# SCH_MX80_I_MOTHERBOARD.net
KiCad netlist of a schematic drawn in EasyEDA
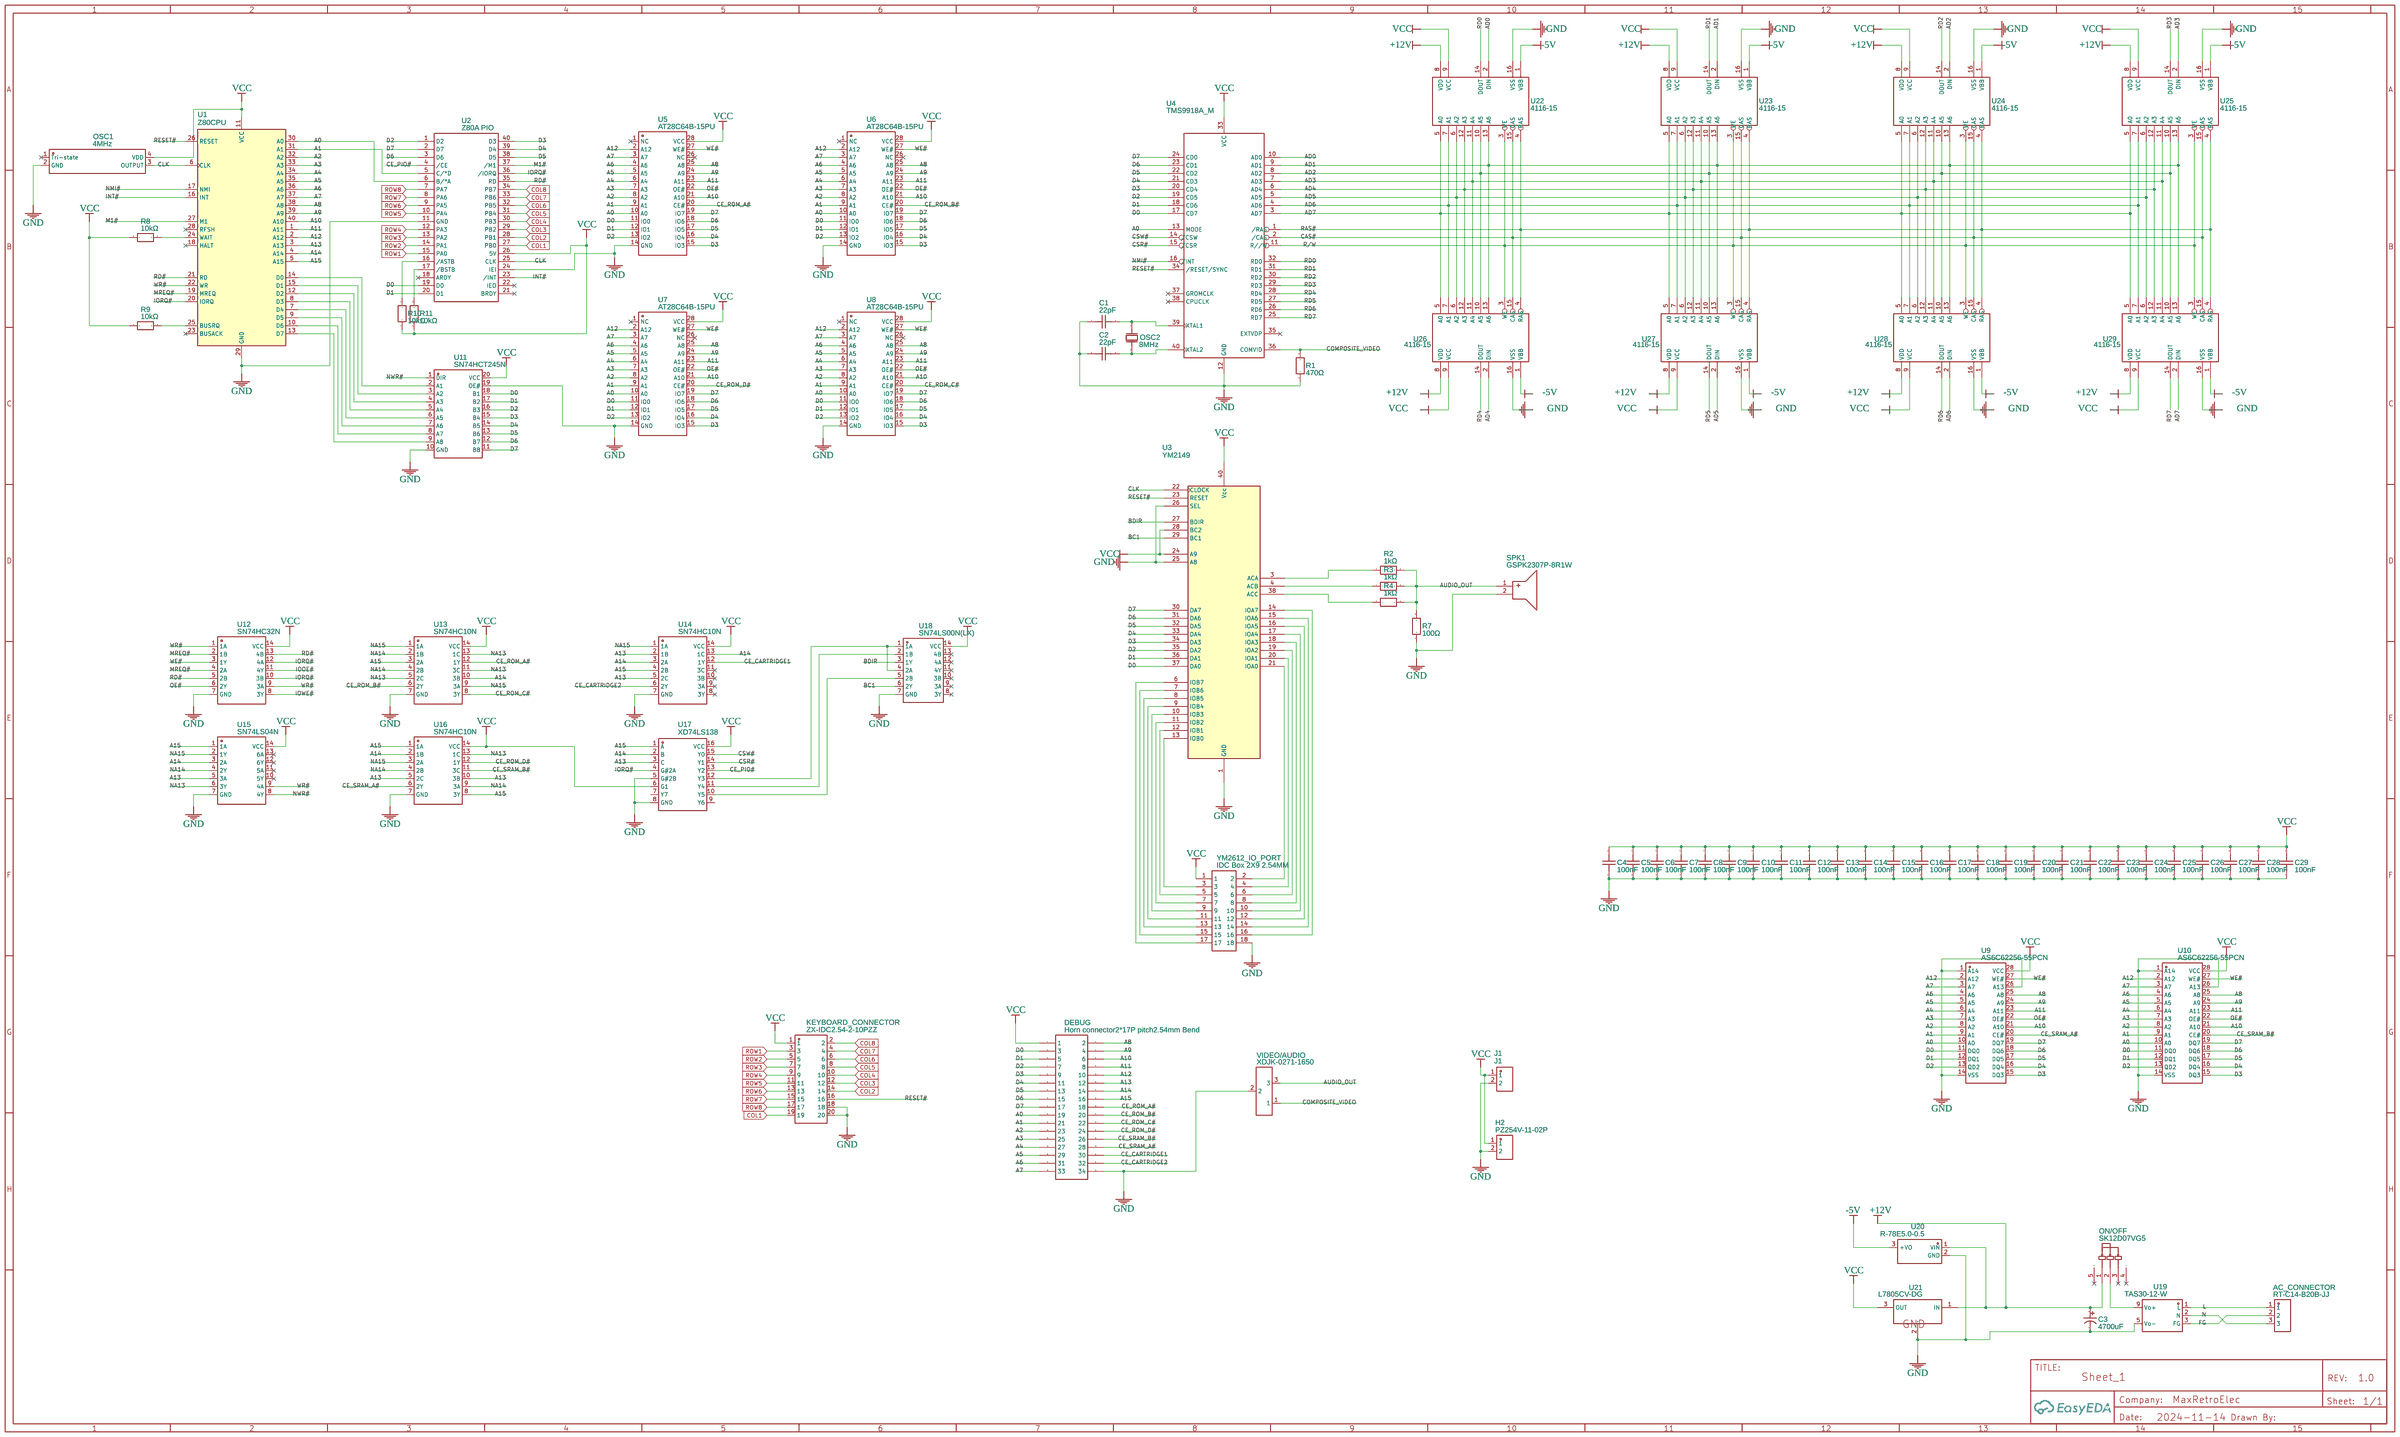
[diagram p0: schematic sheet]

(export (version "E")
  (design (tool "Eeschema 10.0.6"))
  (components
    (comp (ref "AC_CONNECTOR")
      (value "RT-C14-B20B-JJ")
      (fields (field (name "Manufacturer") "Legion(六钧)"))
      (libsource (lib "") (part "RT-C14-B20B-JJ"))
    )
    (comp (ref "C1")
      (value "22pF")
      (fields (field (name "Manufacturer Part") "CC45SL3JD220JYNNA") (field (name "Manufacturer") "TDK"))
      (libsource (lib "") (part "CC45SL3JD220JYNNA"))
    )
    (comp (ref "C2")
      (value "22pF")
      (fields (field (name "Manufacturer Part") "CC45SL3JD220JYNNA") (field (name "Manufacturer") "TDK"))
      (libsource (lib "") (part "CC45SL3JD220JYNNA"))
    )
    (comp (ref "C3")
      (value "4700uF")
      (fields
        (field (name "Manufacturer Part") "KM478M025K30RR0VH2FP0")
        (field (name "Manufacturer") "CX(承兴)")
      )
      (libsource (lib "") (part "4700uF25V"))
    )
    (comp (ref "C4")
      (value "100nF")
      (fields
        (field (name "Manufacturer Part") "CC1H104ZC74D3F5O30MN")
        (field (name "Manufacturer") "Dersonic(德尔创)")
      )
      (libsource (lib "") (part "CC1H104ZC74D3F5O30MN"))
    )
    (comp (ref "C5")
      (value "100nF")
      (fields
        (field (name "Manufacturer Part") "CC1H104ZC74D3F5O30MN")
        (field (name "Manufacturer") "Dersonic(德尔创)")
      )
      (libsource (lib "") (part "CC1H104ZC74D3F5O30MN"))
    )
    (comp (ref "C6")
      (value "100nF")
      (fields
        (field (name "Manufacturer Part") "CC1H104ZC74D3F5O30MN")
        (field (name "Manufacturer") "Dersonic(德尔创)")
      )
      (libsource (lib "") (part "CC1H104ZC74D3F5O30MN"))
    )
    (comp (ref "C7")
      (value "100nF")
      (fields
        (field (name "Manufacturer Part") "CC1H104ZC74D3F5O30MN")
        (field (name "Manufacturer") "Dersonic(德尔创)")
      )
      (libsource (lib "") (part "CC1H104ZC74D3F5O30MN"))
    )
    (comp (ref "C8")
      (value "100nF")
      (fields
        (field (name "Manufacturer Part") "CC1H104ZC74D3F5O30MN")
        (field (name "Manufacturer") "Dersonic(德尔创)")
      )
      (libsource (lib "") (part "CC1H104ZC74D3F5O30MN"))
    )
    (comp (ref "C9")
      (value "100nF")
      (fields
        (field (name "Manufacturer Part") "CC1H104ZC74D3F5O30MN")
        (field (name "Manufacturer") "Dersonic(德尔创)")
      )
      (libsource (lib "") (part "CC1H104ZC74D3F5O30MN"))
    )
    (comp (ref "C10")
      (value "100nF")
      (fields
        (field (name "Manufacturer Part") "CC1H104ZC74D3F5O30MN")
        (field (name "Manufacturer") "Dersonic(德尔创)")
      )
      (libsource (lib "") (part "CC1H104ZC74D3F5O30MN"))
    )
    (comp (ref "C11")
      (value "100nF")
      (fields
        (field (name "Manufacturer Part") "CC1H104ZC74D3F5O30MN")
        (field (name "Manufacturer") "Dersonic(德尔创)")
      )
      (libsource (lib "") (part "CC1H104ZC74D3F5O30MN"))
    )
    (comp (ref "C12")
      (value "100nF")
      (fields
        (field (name "Manufacturer Part") "CC1H104ZC74D3F5O30MN")
        (field (name "Manufacturer") "Dersonic(德尔创)")
      )
      (libsource (lib "") (part "CC1H104ZC74D3F5O30MN"))
    )
    (comp (ref "C13")
      (value "100nF")
      (fields
        (field (name "Manufacturer Part") "CC1H104ZC74D3F5O30MN")
        (field (name "Manufacturer") "Dersonic(德尔创)")
      )
      (libsource (lib "") (part "CC1H104ZC74D3F5O30MN"))
    )
    (comp (ref "C14")
      (value "100nF")
      (fields
        (field (name "Manufacturer Part") "CC1H104ZC74D3F5O30MN")
        (field (name "Manufacturer") "Dersonic(德尔创)")
      )
      (libsource (lib "") (part "CC1H104ZC74D3F5O30MN"))
    )
    (comp (ref "C15")
      (value "100nF")
      (fields
        (field (name "Manufacturer Part") "CC1H104ZC74D3F5O30MN")
        (field (name "Manufacturer") "Dersonic(德尔创)")
      )
      (libsource (lib "") (part "CC1H104ZC74D3F5O30MN"))
    )
    (comp (ref "C16")
      (value "100nF")
      (fields
        (field (name "Manufacturer Part") "CC1H104ZC74D3F5O30MN")
        (field (name "Manufacturer") "Dersonic(德尔创)")
      )
      (libsource (lib "") (part "CC1H104ZC74D3F5O30MN"))
    )
    (comp (ref "C17")
      (value "100nF")
      (fields
        (field (name "Manufacturer Part") "CC1H104ZC74D3F5O30MN")
        (field (name "Manufacturer") "Dersonic(德尔创)")
      )
      (libsource (lib "") (part "CC1H104ZC74D3F5O30MN"))
    )
    (comp (ref "C18")
      (value "100nF")
      (fields
        (field (name "Manufacturer Part") "CC1H104ZC74D3F5O30MN")
        (field (name "Manufacturer") "Dersonic(德尔创)")
      )
      (libsource (lib "") (part "CC1H104ZC74D3F5O30MN"))
    )
    (comp (ref "C19")
      (value "100nF")
      (fields
        (field (name "Manufacturer Part") "CC1H104ZC74D3F5O30MN")
        (field (name "Manufacturer") "Dersonic(德尔创)")
      )
      (libsource (lib "") (part "CC1H104ZC74D3F5O30MN"))
    )
    (comp (ref "C20")
      (value "100nF")
      (fields
        (field (name "Manufacturer Part") "CC1H104ZC74D3F5O30MN")
        (field (name "Manufacturer") "Dersonic(德尔创)")
      )
      (libsource (lib "") (part "CC1H104ZC74D3F5O30MN"))
    )
    (comp (ref "C21")
      (value "100nF")
      (fields
        (field (name "Manufacturer Part") "CC1H104ZC74D3F5O30MN")
        (field (name "Manufacturer") "Dersonic(德尔创)")
      )
      (libsource (lib "") (part "CC1H104ZC74D3F5O30MN"))
    )
    (comp (ref "C22")
      (value "100nF")
      (fields
        (field (name "Manufacturer Part") "CC1H104ZC74D3F5O30MN")
        (field (name "Manufacturer") "Dersonic(德尔创)")
      )
      (libsource (lib "") (part "CC1H104ZC74D3F5O30MN"))
    )
    (comp (ref "C23")
      (value "100nF")
      (fields
        (field (name "Manufacturer Part") "CC1H104ZC74D3F5O30MN")
        (field (name "Manufacturer") "Dersonic(德尔创)")
      )
      (libsource (lib "") (part "CC1H104ZC74D3F5O30MN"))
    )
    (comp (ref "C24")
      (value "100nF")
      (fields
        (field (name "Manufacturer Part") "CC1H104ZC74D3F5O30MN")
        (field (name "Manufacturer") "Dersonic(德尔创)")
      )
      (libsource (lib "") (part "CC1H104ZC74D3F5O30MN"))
    )
    (comp (ref "C25")
      (value "100nF")
      (fields
        (field (name "Manufacturer Part") "CC1H104ZC74D3F5O30MN")
        (field (name "Manufacturer") "Dersonic(德尔创)")
      )
      (libsource (lib "") (part "CC1H104ZC74D3F5O30MN"))
    )
    (comp (ref "C26")
      (value "100nF")
      (fields
        (field (name "Manufacturer Part") "CC1H104ZC74D3F5O30MN")
        (field (name "Manufacturer") "Dersonic(德尔创)")
      )
      (libsource (lib "") (part "CC1H104ZC74D3F5O30MN"))
    )
    (comp (ref "C27")
      (value "100nF")
      (fields
        (field (name "Manufacturer Part") "CC1H104ZC74D3F5O30MN")
        (field (name "Manufacturer") "Dersonic(德尔创)")
      )
      (libsource (lib "") (part "CC1H104ZC74D3F5O30MN"))
    )
    (comp (ref "C28")
      (value "100nF")
      (fields
        (field (name "Manufacturer Part") "CC1H104ZC74D3F5O30MN")
        (field (name "Manufacturer") "Dersonic(德尔创)")
      )
      (libsource (lib "") (part "CC1H104ZC74D3F5O30MN"))
    )
    (comp (ref "C29")
      (value "100nF")
      (fields
        (field (name "Manufacturer Part") "CC1H104ZC74D3F5O30MN")
        (field (name "Manufacturer") "Dersonic(德尔创)")
      )
      (libsource (lib "") (part "CC1H104ZC74D3F5O30MN"))
    )
    (comp (ref "DEBUG")
      (value "Horn connector2*17P pitch2.54mm Bend")
      (fields
        (field (name "Manufacturer Part") "2.54-2*17P弯简牛")
        (field (name "Manufacturer") "BOOMELE(博穆精密)")
      )
      (libsource (lib "") (part "Horn connector2*17P pitch2.54mm Bend"))
    )
    (comp (ref "H2")
      (value "PZ254V-11-02P")
      (fields (field (name "Manufacturer") "XFCN(兴飞)"))
      (libsource (lib "") (part "PZ254V-11-02P"))
    )
    (comp (ref "J1")
      (value "J1")
      (fields
        (field (name "Manufacturer Part") "ZX-PM2.54-1-2PY")
        (field (name "Manufacturer") "Megastar(兆星)")
      )
      (libsource (lib "") (part "ZX-PM2.54-1-2PY"))
    )
    (comp (ref "KEYBOARD_CONNECTOR")
      (value "ZX-IDC2.54-2-10PZZ")
      (fields (field (name "Manufacturer") "Megastar(兆星)"))
      (libsource (lib "") (part "ZX-IDC2.54-2-10PZZ"))
    )
    (comp (ref "ON/OFF")
      (value "SK12D07VG5")
      (fields (field (name "Manufacturer") "SHOU HAN(首韩)"))
      (libsource (lib "") (part "SK12D07VG5"))
    )
    (comp (ref "OSC1")
      (value "4MHz")
      (fields
        (field (name "Manufacturer Part") "S7D4.000000B20F30T")
        (field (name "Manufacturer") "SCTF(星通时频)")
      )
      (libsource (lib "") (part "S7D4.000000B20F30T"))
    )
    (comp (ref "OSC2")
      (value "8MHz")
      (fields (field (name "Manufacturer Part") "X49SD8MSD2SC") (field (name "Manufacturer") "YXC(扬兴晶振)"))
      (libsource (lib "") (part "X49SD8MSD2SC"))
    )
    (comp (ref "R1")
      (value "470Ω")
      (fields (field (name "Manufacturer Part") "CF1/4W-470Ω±5%T52") (field (name "Manufacturer") "华星机电"))
      (libsource (lib "") (part "CF1/4W-470Ω±5%T52"))
    )
    (comp (ref "R2")
      (value "1kΩ")
      (fields (field (name "Manufacturer Part") "CR1/4W-1K±5%-ST52") (field (name "Manufacturer") "VO(翔胜)"))
      (libsource (lib "") (part "CR1/4W-1K±5%-ST52"))
    )
    (comp (ref "R3")
      (value "1kΩ")
      (fields (field (name "Manufacturer Part") "CR1/4W-1K±5%-ST52") (field (name "Manufacturer") "VO(翔胜)"))
      (libsource (lib "") (part "CR1/4W-1K±5%-ST52"))
    )
    (comp (ref "R4")
      (value "1kΩ")
      (fields (field (name "Manufacturer Part") "CR1/4W-1K±5%-ST52") (field (name "Manufacturer") "VO(翔胜)"))
      (libsource (lib "") (part "CR1/4W-1K±5%-ST52"))
    )
    (comp (ref "R7")
      (value "100Ω")
      (fields (field (name "Manufacturer Part") "CR1/4W-100Ω±5%-ST52") (field (name "Manufacturer") "VO(翔胜)"))
      (libsource (lib "") (part "CR1/4W-100Ω±5%-ST52"))
    )
    (comp (ref "R8")
      (value "10kΩ")
      (fields (field (name "Manufacturer Part") "CR1/4W-10K±5%-ST52") (field (name "Manufacturer") "VO(翔胜)"))
      (libsource (lib "") (part "CR1/4W-10K±5%-ST52_1"))
    )
    (comp (ref "R9")
      (value "10kΩ")
      (fields (field (name "Manufacturer Part") "CR1/4W-10K±5%-ST52") (field (name "Manufacturer") "VO(翔胜)"))
      (libsource (lib "") (part "CR1/4W-10K±5%-ST52_1"))
    )
    (comp (ref "R10")
      (value "10kΩ")
      (fields (field (name "Manufacturer Part") "CR1/4W-10K±5%-ST52") (field (name "Manufacturer") "VO(翔胜)"))
      (libsource (lib "") (part "CR1/4W-10K±5%-ST52"))
    )
    (comp (ref "R11")
      (value "10kΩ")
      (fields (field (name "Manufacturer Part") "CR1/4W-10K±5%-ST52") (field (name "Manufacturer") "VO(翔胜)"))
      (libsource (lib "") (part "CR1/4W-10K±5%-ST52"))
    )
    (comp (ref "SPK1")
      (value "GSPK2307P-8R1W")
      (fields (field (name "Manufacturer") "INGHAi(赢海)"))
      (libsource (lib "") (part "GSPK2307P-8R1W"))
    )
    (comp (ref "U1") (value "Z80CPU") (libsource (lib "") (part "Z80CPU")))
    (comp (ref "U2") (value "Z80A PIO") (libsource (lib "") (part "Z80A PIO")))
    (comp (ref "U3") (value "YM2149") (libsource (lib "") (part "YM2149")))
    (comp (ref "U4") (value "TMS9918A_M") (libsource (lib "") (part "TMS9918A_M")))
    (comp (ref "U5")
      (value "AT28C64B-15PU")
      (fields (field (name "Manufacturer") "MICROCHIP(美国微芯)"))
      (libsource (lib "") (part "AT28C64B-15PU"))
    )
    (comp (ref "U6")
      (value "AT28C64B-15PU")
      (fields (field (name "Manufacturer") "MICROCHIP(美国微芯)"))
      (libsource (lib "") (part "AT28C64B-15PU"))
    )
    (comp (ref "U7")
      (value "AT28C64B-15PU")
      (fields (field (name "Manufacturer") "MICROCHIP(美国微芯)"))
      (libsource (lib "") (part "AT28C64B-15PU"))
    )
    (comp (ref "U8")
      (value "AT28C64B-15PU")
      (fields (field (name "Manufacturer") "MICROCHIP(美国微芯)"))
      (libsource (lib "") (part "AT28C64B-15PU"))
    )
    (comp (ref "U9")
      (value "AS6C62256-55PCN")
      (fields (field (name "Manufacturer") "Alliance Memory"))
      (libsource (lib "") (part "AS6C62256-55PCN"))
    )
    (comp (ref "U10")
      (value "AS6C62256-55PCN")
      (fields (field (name "Manufacturer") "Alliance Memory"))
      (libsource (lib "") (part "AS6C62256-55PCN"))
    )
    (comp (ref "U11")
      (value "SN74HCT245N")
      (fields (field (name "Manufacturer") "TI(德州仪器)"))
      (libsource (lib "") (part "SN74HCT245N"))
    )
    (comp (ref "U12")
      (value "SN74HC32N")
      (fields (field (name "Manufacturer") "TI(德州仪器)"))
      (libsource (lib "") (part "SN74HC32N"))
    )
    (comp (ref "U13")
      (value "SN74HC10N")
      (fields (field (name "Manufacturer") "TI(德州仪器)"))
      (libsource (lib "") (part "SN74HC10N"))
    )
    (comp (ref "U14")
      (value "SN74HC10N")
      (fields (field (name "Manufacturer") "TI(德州仪器)"))
      (libsource (lib "") (part "SN74HC10N"))
    )
    (comp (ref "U15")
      (value "SN74LS04N")
      (fields (field (name "Manufacturer") "TI(德州仪器)"))
      (libsource (lib "") (part "SN74LS04N"))
    )
    (comp (ref "U16")
      (value "SN74HC10N")
      (fields (field (name "Manufacturer") "TI(德州仪器)"))
      (libsource (lib "") (part "SN74HC10N"))
    )
    (comp (ref "U17")
      (value "XD74LS138")
      (fields (field (name "Manufacturer") "XINLUDA(信路达)"))
      (libsource (lib "") (part "XD74LS138"))
    )
    (comp (ref "U18")
      (value "SN74LS00N(LX)")
      (fields (field (name "Manufacturer") "LX(灵星芯微)"))
      (libsource (lib "") (part "SN74LS00N(LX)"))
    )
    (comp (ref "U19")
      (value "TAS30-12-W")
      (fields (field (name "Manufacturer") "TDPOWER(腾达电源)"))
      (libsource (lib "") (part "TAS30-12-W"))
    )
    (comp (ref "U20")
      (value "R-78E5.0-0.5")
      (fields (field (name "Manufacturer") "YLPTEC(易川)"))
      (libsource (lib "") (part "R-78E5.0-0.5"))
    )
    (comp (ref "U21")
      (value "L7805CV-DG")
      (fields (field (name "Manufacturer") "ST(意法半导体)"))
      (libsource (lib "") (part "L7805CV-DG"))
    )
    (comp (ref "U22")
      (value "4116-15")
      (fields (field (name "Manufacturer") "Major Brands"))
      (libsource (lib "") (part "4116-15"))
    )
    (comp (ref "U23")
      (value "4116-15")
      (fields (field (name "Manufacturer") "Major Brands"))
      (libsource (lib "") (part "4116-15"))
    )
    (comp (ref "U24")
      (value "4116-15")
      (fields (field (name "Manufacturer") "Major Brands"))
      (libsource (lib "") (part "4116-15"))
    )
    (comp (ref "U25")
      (value "4116-15")
      (fields (field (name "Manufacturer") "Major Brands"))
      (libsource (lib "") (part "4116-15"))
    )
    (comp (ref "U26")
      (value "4116-15")
      (fields (field (name "Manufacturer") "Major Brands"))
      (libsource (lib "") (part "4116-15_1"))
    )
    (comp (ref "U27")
      (value "4116-15")
      (fields (field (name "Manufacturer") "Major Brands"))
      (libsource (lib "") (part "4116-15_1"))
    )
    (comp (ref "U28")
      (value "4116-15")
      (fields (field (name "Manufacturer") "Major Brands"))
      (libsource (lib "") (part "4116-15_1"))
    )
    (comp (ref "U29")
      (value "4116-15")
      (fields (field (name "Manufacturer") "Major Brands"))
      (libsource (lib "") (part "4116-15_1"))
    )
    (comp (ref "VIDEO/AUDIO")
      (value "XDJK-0271-1650")
      (fields (field (name "Manufacturer") "LX(连欣科技)"))
      (libsource (lib "") (part "XDJK-0271-1650"))
    )
    (comp (ref "YM2612_IO_PORT")
      (value "IDC Box 2X9 2.54MM")
      (fields
        (field (name "Manufacturer Part") "2.54-2*9P 弯 简牛")
        (field (name "Manufacturer") "BOOMELE(博穆精密)")
      )
      (libsource (lib "") (part "IDC Box 2X9 2.54MM"))
    )
  )
  (nets
    (net (code "1") (name "+12V") (class "Default")
      (node (ref "C3") (pin "1") (pinfunction "1_1") (pintype "input"))
      (node (ref "ON/OFF") (pin "1") (pinfunction "1_1") (pintype "unspecified"))
      (node (ref "U20") (pin "1") (pinfunction "VIN_1") (pintype "unspecified"))
      (node (ref "U21") (pin "1") (pinfunction "IN_1") (pintype "passive"))
      (node (ref "U22") (pin "8") (pinfunction "VDD_8") (pintype "unspecified"))
      (node (ref "U23") (pin "8") (pinfunction "VDD_8") (pintype "unspecified"))
      (node (ref "U24") (pin "8") (pinfunction "VDD_8") (pintype "unspecified"))
      (node (ref "U25") (pin "8") (pinfunction "VDD_8") (pintype "unspecified"))
      (node (ref "U26") (pin "8") (pinfunction "VDD_8") (pintype "unspecified"))
      (node (ref "U27") (pin "8") (pinfunction "VDD_8") (pintype "unspecified"))
      (node (ref "U28") (pin "8") (pinfunction "VDD_8") (pintype "unspecified"))
      (node (ref "U29") (pin "8") (pinfunction "VDD_8") (pintype "unspecified"))
    )
    (net (code "2") (name "-5V") (class "Default")
      (node (ref "U20") (pin "3") (pinfunction "+VO_3") (pintype "unspecified"))
      (node (ref "U22") (pin "1") (pinfunction "VBB_1") (pintype "unspecified"))
      (node (ref "U23") (pin "1") (pinfunction "VBB_1") (pintype "unspecified"))
      (node (ref "U24") (pin "1") (pinfunction "VBB_1") (pintype "unspecified"))
      (node (ref "U25") (pin "1") (pinfunction "VBB_1") (pintype "unspecified"))
      (node (ref "U26") (pin "1") (pinfunction "VBB_1") (pintype "unspecified"))
      (node (ref "U27") (pin "1") (pinfunction "VBB_1") (pintype "unspecified"))
      (node (ref "U28") (pin "1") (pinfunction "VBB_1") (pintype "unspecified"))
      (node (ref "U29") (pin "1") (pinfunction "VBB_1") (pintype "unspecified"))
    )
    (net (code "3") (name "/A0") (class "Default")
      (node (ref "DEBUG") (pin "19") (pinfunction "19_19") (pintype "unspecified"))
      (node (ref "U1") (pin "30") (pinfunction "A0_30") (pintype "output"))
      (node (ref "U10") (pin "10") (pinfunction "A0_10") (pintype "unspecified"))
      (node (ref "U2") (pin "6") (pinfunction "B/*A_6") (pintype "unspecified"))
      (node (ref "U4") (pin "13") (pinfunction "MODE_13") (pintype "unspecified"))
      (node (ref "U5") (pin "10") (pinfunction "A0_10") (pintype "unspecified"))
      (node (ref "U6") (pin "10") (pinfunction "A0_10") (pintype "unspecified"))
      (node (ref "U7") (pin "10") (pinfunction "A0_10") (pintype "unspecified"))
      (node (ref "U8") (pin "10") (pinfunction "A0_10") (pintype "unspecified"))
      (node (ref "U9") (pin "10") (pinfunction "A0_10") (pintype "unspecified"))
    )
    (net (code "4") (name "/A1") (class "Default")
      (node (ref "DEBUG") (pin "21") (pinfunction "21_21") (pintype "unspecified"))
      (node (ref "U1") (pin "31") (pinfunction "A1_31") (pintype "output"))
      (node (ref "U10") (pin "9") (pinfunction "A1_9") (pintype "unspecified"))
      (node (ref "U2") (pin "5") (pinfunction "C/*D_5") (pintype "unspecified"))
      (node (ref "U5") (pin "9") (pinfunction "A1_9") (pintype "unspecified"))
      (node (ref "U6") (pin "9") (pinfunction "A1_9") (pintype "unspecified"))
      (node (ref "U7") (pin "9") (pinfunction "A1_9") (pintype "unspecified"))
      (node (ref "U8") (pin "9") (pinfunction "A1_9") (pintype "unspecified"))
      (node (ref "U9") (pin "9") (pinfunction "A1_9") (pintype "unspecified"))
    )
    (net (code "5") (name "/A2") (class "Default")
      (node (ref "DEBUG") (pin "23") (pinfunction "23_23") (pintype "unspecified"))
      (node (ref "U1") (pin "32") (pinfunction "A2_32") (pintype "output"))
      (node (ref "U10") (pin "8") (pinfunction "A2_8") (pintype "unspecified"))
      (node (ref "U5") (pin "8") (pinfunction "A2_8") (pintype "unspecified"))
      (node (ref "U6") (pin "8") (pinfunction "A2_8") (pintype "unspecified"))
      (node (ref "U7") (pin "8") (pinfunction "A2_8") (pintype "unspecified"))
      (node (ref "U8") (pin "8") (pinfunction "A2_8") (pintype "unspecified"))
      (node (ref "U9") (pin "8") (pinfunction "A2_8") (pintype "unspecified"))
    )
    (net (code "6") (name "/A3") (class "Default")
      (node (ref "DEBUG") (pin "25") (pinfunction "25_25") (pintype "unspecified"))
      (node (ref "U1") (pin "33") (pinfunction "A3_33") (pintype "output"))
      (node (ref "U10") (pin "7") (pinfunction "A3_7") (pintype "unspecified"))
      (node (ref "U5") (pin "7") (pinfunction "A3_7") (pintype "unspecified"))
      (node (ref "U6") (pin "7") (pinfunction "A3_7") (pintype "unspecified"))
      (node (ref "U7") (pin "7") (pinfunction "A3_7") (pintype "unspecified"))
      (node (ref "U8") (pin "7") (pinfunction "A3_7") (pintype "unspecified"))
      (node (ref "U9") (pin "7") (pinfunction "A3_7") (pintype "unspecified"))
    )
    (net (code "7") (name "/A4") (class "Default")
      (node (ref "DEBUG") (pin "27") (pinfunction "27_27") (pintype "unspecified"))
      (node (ref "U1") (pin "34") (pinfunction "A4_34") (pintype "output"))
      (node (ref "U10") (pin "6") (pinfunction "A4_6") (pintype "unspecified"))
      (node (ref "U5") (pin "6") (pinfunction "A4_6") (pintype "unspecified"))
      (node (ref "U6") (pin "6") (pinfunction "A4_6") (pintype "unspecified"))
      (node (ref "U7") (pin "6") (pinfunction "A4_6") (pintype "unspecified"))
      (node (ref "U8") (pin "6") (pinfunction "A4_6") (pintype "unspecified"))
      (node (ref "U9") (pin "6") (pinfunction "A4_6") (pintype "unspecified"))
    )
    (net (code "8") (name "/A5") (class "Default")
      (node (ref "DEBUG") (pin "29") (pinfunction "29_29") (pintype "unspecified"))
      (node (ref "U1") (pin "35") (pinfunction "A5_35") (pintype "output"))
      (node (ref "U10") (pin "5") (pinfunction "A5_5") (pintype "unspecified"))
      (node (ref "U5") (pin "5") (pinfunction "A5_5") (pintype "unspecified"))
      (node (ref "U6") (pin "5") (pinfunction "A5_5") (pintype "unspecified"))
      (node (ref "U7") (pin "5") (pinfunction "A5_5") (pintype "unspecified"))
      (node (ref "U8") (pin "5") (pinfunction "A5_5") (pintype "unspecified"))
      (node (ref "U9") (pin "5") (pinfunction "A5_5") (pintype "unspecified"))
    )
    (net (code "9") (name "/A6") (class "Default")
      (node (ref "DEBUG") (pin "31") (pinfunction "31_31") (pintype "unspecified"))
      (node (ref "U1") (pin "36") (pinfunction "A6_36") (pintype "output"))
      (node (ref "U10") (pin "4") (pinfunction "A6_4") (pintype "unspecified"))
      (node (ref "U5") (pin "4") (pinfunction "A6_4") (pintype "unspecified"))
      (node (ref "U6") (pin "4") (pinfunction "A6_4") (pintype "unspecified"))
      (node (ref "U7") (pin "4") (pinfunction "A6_4") (pintype "unspecified"))
      (node (ref "U8") (pin "4") (pinfunction "A6_4") (pintype "unspecified"))
      (node (ref "U9") (pin "4") (pinfunction "A6_4") (pintype "unspecified"))
    )
    (net (code "10") (name "/A7") (class "Default")
      (node (ref "DEBUG") (pin "33") (pinfunction "33_33") (pintype "unspecified"))
      (node (ref "U1") (pin "37") (pinfunction "A7_37") (pintype "output"))
      (node (ref "U10") (pin "3") (pinfunction "A7_3") (pintype "unspecified"))
      (node (ref "U5") (pin "3") (pinfunction "A7_3") (pintype "unspecified"))
      (node (ref "U6") (pin "3") (pinfunction "A7_3") (pintype "unspecified"))
      (node (ref "U7") (pin "3") (pinfunction "A7_3") (pintype "unspecified"))
      (node (ref "U8") (pin "3") (pinfunction "A7_3") (pintype "unspecified"))
      (node (ref "U9") (pin "3") (pinfunction "A7_3") (pintype "unspecified"))
    )
    (net (code "11") (name "/A8") (class "Default")
      (node (ref "DEBUG") (pin "2") (pinfunction "2_2") (pintype "unspecified"))
      (node (ref "U1") (pin "38") (pinfunction "A8_38") (pintype "output"))
      (node (ref "U10") (pin "25") (pinfunction "A8_25") (pintype "unspecified"))
      (node (ref "U5") (pin "25") (pinfunction "A8_25") (pintype "unspecified"))
      (node (ref "U6") (pin "25") (pinfunction "A8_25") (pintype "unspecified"))
      (node (ref "U7") (pin "25") (pinfunction "A8_25") (pintype "unspecified"))
      (node (ref "U8") (pin "25") (pinfunction "A8_25") (pintype "unspecified"))
      (node (ref "U9") (pin "25") (pinfunction "A8_25") (pintype "unspecified"))
    )
    (net (code "12") (name "/A9") (class "Default")
      (node (ref "DEBUG") (pin "4") (pinfunction "4_4") (pintype "unspecified"))
      (node (ref "U1") (pin "39") (pinfunction "A9_39") (pintype "output"))
      (node (ref "U10") (pin "24") (pinfunction "A9_24") (pintype "unspecified"))
      (node (ref "U5") (pin "24") (pinfunction "A9_24") (pintype "unspecified"))
      (node (ref "U6") (pin "24") (pinfunction "A9_24") (pintype "unspecified"))
      (node (ref "U7") (pin "24") (pinfunction "A9_24") (pintype "unspecified"))
      (node (ref "U8") (pin "24") (pinfunction "A9_24") (pintype "unspecified"))
      (node (ref "U9") (pin "24") (pinfunction "A9_24") (pintype "unspecified"))
    )
    (net (code "13") (name "/A10") (class "Default")
      (node (ref "DEBUG") (pin "6") (pinfunction "6_6") (pintype "unspecified"))
      (node (ref "U1") (pin "40") (pinfunction "A10_40") (pintype "output"))
      (node (ref "U10") (pin "21") (pinfunction "A10_21") (pintype "unspecified"))
      (node (ref "U5") (pin "21") (pinfunction "A10_21") (pintype "unspecified"))
      (node (ref "U6") (pin "21") (pinfunction "A10_21") (pintype "unspecified"))
      (node (ref "U7") (pin "21") (pinfunction "A10_21") (pintype "unspecified"))
      (node (ref "U8") (pin "21") (pinfunction "A10_21") (pintype "unspecified"))
      (node (ref "U9") (pin "21") (pinfunction "A10_21") (pintype "unspecified"))
    )
    (net (code "14") (name "/A11") (class "Default")
      (node (ref "DEBUG") (pin "8") (pinfunction "8_8") (pintype "unspecified"))
      (node (ref "U1") (pin "1") (pinfunction "A11_1") (pintype "output"))
      (node (ref "U10") (pin "23") (pinfunction "A11_23") (pintype "unspecified"))
      (node (ref "U5") (pin "23") (pinfunction "A11_23") (pintype "unspecified"))
      (node (ref "U6") (pin "23") (pinfunction "A11_23") (pintype "unspecified"))
      (node (ref "U7") (pin "23") (pinfunction "A11_23") (pintype "unspecified"))
      (node (ref "U8") (pin "23") (pinfunction "A11_23") (pintype "unspecified"))
      (node (ref "U9") (pin "23") (pinfunction "A11_23") (pintype "unspecified"))
    )
    (net (code "15") (name "/A12") (class "Default")
      (node (ref "DEBUG") (pin "10") (pinfunction "10_10") (pintype "unspecified"))
      (node (ref "U1") (pin "2") (pinfunction "A12_2") (pintype "output"))
      (node (ref "U10") (pin "2") (pinfunction "A12_2") (pintype "unspecified"))
      (node (ref "U5") (pin "2") (pinfunction "A12_2") (pintype "unspecified"))
      (node (ref "U6") (pin "2") (pinfunction "A12_2") (pintype "unspecified"))
      (node (ref "U7") (pin "2") (pinfunction "A12_2") (pintype "unspecified"))
      (node (ref "U8") (pin "2") (pinfunction "A12_2") (pintype "unspecified"))
      (node (ref "U9") (pin "2") (pinfunction "A12_2") (pintype "unspecified"))
    )
    (net (code "16") (name "/A13") (class "Default")
      (node (ref "DEBUG") (pin "12") (pinfunction "12_12") (pintype "unspecified"))
      (node (ref "U1") (pin "3") (pinfunction "A13_3") (pintype "output"))
      (node (ref "U14") (pin "2") (pinfunction "1B_2") (pintype "unspecified"))
      (node (ref "U14") (pin "5") (pinfunction "2C_5") (pintype "unspecified"))
      (node (ref "U15") (pin "5") (pinfunction "3A_5") (pintype "unspecified"))
      (node (ref "U16") (pin "10") (pinfunction "3B_10") (pintype "unspecified"))
      (node (ref "U16") (pin "5") (pinfunction "2C_5") (pintype "unspecified"))
      (node (ref "U17") (pin "3") (pinfunction "C_3") (pintype "unspecified"))
    )
    (net (code "17") (name "/A14") (class "Default")
      (node (ref "DEBUG") (pin "14") (pinfunction "14_14") (pintype "unspecified"))
      (node (ref "U1") (pin "4") (pinfunction "A14_4") (pintype "output"))
      (node (ref "U13") (pin "10") (pinfunction "3B_10") (pintype "unspecified"))
      (node (ref "U14") (pin "13") (pinfunction "1C_13") (pintype "unspecified"))
      (node (ref "U14") (pin "3") (pinfunction "2A_3") (pintype "unspecified"))
      (node (ref "U15") (pin "3") (pinfunction "2A_3") (pintype "unspecified"))
      (node (ref "U16") (pin "2") (pinfunction "1B_2") (pintype "unspecified"))
      (node (ref "U17") (pin "2") (pinfunction "B_2") (pintype "unspecified"))
    )
    (net (code "18") (name "/A15") (class "Default")
      (node (ref "DEBUG") (pin "16") (pinfunction "16_16") (pintype "unspecified"))
      (node (ref "U1") (pin "5") (pinfunction "A15_5") (pintype "output"))
      (node (ref "U13") (pin "3") (pinfunction "2A_3") (pintype "unspecified"))
      (node (ref "U14") (pin "4") (pinfunction "2B_4") (pintype "unspecified"))
      (node (ref "U15") (pin "1") (pinfunction "1A_1") (pintype "unspecified"))
      (node (ref "U16") (pin "1") (pinfunction "1A_1") (pintype "unspecified"))
      (node (ref "U16") (pin "8") (pinfunction "3Y_8") (pintype "unspecified"))
      (node (ref "U17") (pin "1") (pinfunction "A_1") (pintype "unspecified"))
    )
    (net (code "19") (name "/AD0") (class "Default")
      (node (ref "U22") (pin "2") (pinfunction "DIN_2") (pintype "unspecified"))
      (node (ref "U4") (pin "10") (pinfunction "AD0_10") (pintype "unspecified"))
    )
    (net (code "20") (name "/AD1") (class "Default")
      (node (ref "U22") (pin "13") (pinfunction "A6_13") (pintype "unspecified"))
      (node (ref "U23") (pin "13") (pinfunction "A6_13") (pintype "unspecified"))
      (node (ref "U23") (pin "2") (pinfunction "DIN_2") (pintype "unspecified"))
      (node (ref "U24") (pin "13") (pinfunction "A6_13") (pintype "unspecified"))
      (node (ref "U25") (pin "13") (pinfunction "A6_13") (pintype "unspecified"))
      (node (ref "U26") (pin "13") (pinfunction "A6_13") (pintype "unspecified"))
      (node (ref "U27") (pin "13") (pinfunction "A6_13") (pintype "unspecified"))
      (node (ref "U28") (pin "13") (pinfunction "A6_13") (pintype "unspecified"))
      (node (ref "U29") (pin "13") (pinfunction "A6_13") (pintype "unspecified"))
      (node (ref "U4") (pin "9") (pinfunction "AD1_9") (pintype "unspecified"))
    )
    (net (code "21") (name "/AD2") (class "Default")
      (node (ref "U22") (pin "10") (pinfunction "A5_10") (pintype "unspecified"))
      (node (ref "U23") (pin "10") (pinfunction "A5_10") (pintype "unspecified"))
      (node (ref "U24") (pin "10") (pinfunction "A5_10") (pintype "unspecified"))
      (node (ref "U24") (pin "2") (pinfunction "DIN_2") (pintype "unspecified"))
      (node (ref "U25") (pin "10") (pinfunction "A5_10") (pintype "unspecified"))
      (node (ref "U26") (pin "10") (pinfunction "A5_10") (pintype "unspecified"))
      (node (ref "U27") (pin "10") (pinfunction "A5_10") (pintype "unspecified"))
      (node (ref "U28") (pin "10") (pinfunction "A5_10") (pintype "unspecified"))
      (node (ref "U29") (pin "10") (pinfunction "A5_10") (pintype "unspecified"))
      (node (ref "U4") (pin "8") (pinfunction "AD2_8") (pintype "unspecified"))
    )
    (net (code "22") (name "/AD3") (class "Default")
      (node (ref "U22") (pin "11") (pinfunction "A4_11") (pintype "unspecified"))
      (node (ref "U23") (pin "11") (pinfunction "A4_11") (pintype "unspecified"))
      (node (ref "U24") (pin "11") (pinfunction "A4_11") (pintype "unspecified"))
      (node (ref "U25") (pin "11") (pinfunction "A4_11") (pintype "unspecified"))
      (node (ref "U25") (pin "2") (pinfunction "DIN_2") (pintype "unspecified"))
      (node (ref "U26") (pin "11") (pinfunction "A4_11") (pintype "unspecified"))
      (node (ref "U27") (pin "11") (pinfunction "A4_11") (pintype "unspecified"))
      (node (ref "U28") (pin "11") (pinfunction "A4_11") (pintype "unspecified"))
      (node (ref "U29") (pin "11") (pinfunction "A4_11") (pintype "unspecified"))
      (node (ref "U4") (pin "7") (pinfunction "AD3_7") (pintype "unspecified"))
    )
    (net (code "23") (name "/AD4") (class "Default")
      (node (ref "U22") (pin "12") (pinfunction "A3_12") (pintype "unspecified"))
      (node (ref "U23") (pin "12") (pinfunction "A3_12") (pintype "unspecified"))
      (node (ref "U24") (pin "12") (pinfunction "A3_12") (pintype "unspecified"))
      (node (ref "U25") (pin "12") (pinfunction "A3_12") (pintype "unspecified"))
      (node (ref "U26") (pin "12") (pinfunction "A3_12") (pintype "unspecified"))
      (node (ref "U26") (pin "2") (pinfunction "DIN_2") (pintype "unspecified"))
      (node (ref "U27") (pin "12") (pinfunction "A3_12") (pintype "unspecified"))
      (node (ref "U28") (pin "12") (pinfunction "A3_12") (pintype "unspecified"))
      (node (ref "U29") (pin "12") (pinfunction "A3_12") (pintype "unspecified"))
      (node (ref "U4") (pin "6") (pinfunction "AD4_6") (pintype "unspecified"))
    )
    (net (code "24") (name "/AD5") (class "Default")
      (node (ref "U22") (pin "6") (pinfunction "A2_6") (pintype "unspecified"))
      (node (ref "U23") (pin "6") (pinfunction "A2_6") (pintype "unspecified"))
      (node (ref "U24") (pin "6") (pinfunction "A2_6") (pintype "unspecified"))
      (node (ref "U25") (pin "6") (pinfunction "A2_6") (pintype "unspecified"))
      (node (ref "U26") (pin "6") (pinfunction "A2_6") (pintype "unspecified"))
      (node (ref "U27") (pin "2") (pinfunction "DIN_2") (pintype "unspecified"))
      (node (ref "U27") (pin "6") (pinfunction "A2_6") (pintype "unspecified"))
      (node (ref "U28") (pin "6") (pinfunction "A2_6") (pintype "unspecified"))
      (node (ref "U29") (pin "6") (pinfunction "A2_6") (pintype "unspecified"))
      (node (ref "U4") (pin "5") (pinfunction "AD5_5") (pintype "unspecified"))
    )
    (net (code "25") (name "/AD6") (class "Default")
      (node (ref "U22") (pin "7") (pinfunction "A1_7") (pintype "unspecified"))
      (node (ref "U23") (pin "7") (pinfunction "A1_7") (pintype "unspecified"))
      (node (ref "U24") (pin "7") (pinfunction "A1_7") (pintype "unspecified"))
      (node (ref "U25") (pin "7") (pinfunction "A1_7") (pintype "unspecified"))
      (node (ref "U26") (pin "7") (pinfunction "A1_7") (pintype "unspecified"))
      (node (ref "U27") (pin "7") (pinfunction "A1_7") (pintype "unspecified"))
      (node (ref "U28") (pin "2") (pinfunction "DIN_2") (pintype "unspecified"))
      (node (ref "U28") (pin "7") (pinfunction "A1_7") (pintype "unspecified"))
      (node (ref "U29") (pin "7") (pinfunction "A1_7") (pintype "unspecified"))
      (node (ref "U4") (pin "4") (pinfunction "AD6_4") (pintype "unspecified"))
    )
    (net (code "26") (name "/AD7") (class "Default")
      (node (ref "U22") (pin "5") (pinfunction "A0_5") (pintype "unspecified"))
      (node (ref "U23") (pin "5") (pinfunction "A0_5") (pintype "unspecified"))
      (node (ref "U24") (pin "5") (pinfunction "A0_5") (pintype "unspecified"))
      (node (ref "U25") (pin "5") (pinfunction "A0_5") (pintype "unspecified"))
      (node (ref "U26") (pin "5") (pinfunction "A0_5") (pintype "unspecified"))
      (node (ref "U27") (pin "5") (pinfunction "A0_5") (pintype "unspecified"))
      (node (ref "U28") (pin "5") (pinfunction "A0_5") (pintype "unspecified"))
      (node (ref "U29") (pin "2") (pinfunction "DIN_2") (pintype "unspecified"))
      (node (ref "U29") (pin "5") (pinfunction "A0_5") (pintype "unspecified"))
      (node (ref "U4") (pin "3") (pinfunction "AD7_3") (pintype "unspecified"))
    )
    (net (code "27") (name "/AUDIO_OUT") (class "Default")
      (node (ref "R2") (pin "2") (pinfunction "2_2") (pintype "unspecified"))
      (node (ref "R3") (pin "2") (pinfunction "2_2") (pintype "unspecified"))
      (node (ref "R4") (pin "2") (pinfunction "2_2") (pintype "unspecified"))
      (node (ref "R7") (pin "2") (pinfunction "2_2") (pintype "unspecified"))
      (node (ref "SPK1") (pin "1") (pinfunction "+_1") (pintype "unspecified"))
      (node (ref "VIDEO/AUDIO") (pin "3") (pinfunction "3_3") (pintype "unspecified"))
    )
    (net (code "28") (name "/BC1") (class "Default")
      (node (ref "U18") (pin "6") (pinfunction "2Y_6") (pintype "unspecified"))
      (node (ref "U3") (pin "29") (pinfunction "BC1_29") (pintype "input"))
    )
    (net (code "29") (name "/BDIR") (class "Default")
      (node (ref "U18") (pin "3") (pinfunction "1Y_3") (pintype "unspecified"))
      (node (ref "U3") (pin "27") (pinfunction "BDIR_27") (pintype "input"))
    )
    (net (code "30") (name "/CAS#") (class "Default")
      (node (ref "U22") (pin "15") (pinfunction "CAS_15") (pintype "unspecified"))
      (node (ref "U23") (pin "15") (pinfunction "CAS_15") (pintype "unspecified"))
      (node (ref "U24") (pin "15") (pinfunction "CAS_15") (pintype "unspecified"))
      (node (ref "U25") (pin "15") (pinfunction "CAS_15") (pintype "unspecified"))
      (node (ref "U26") (pin "15") (pinfunction "CAS_15") (pintype "unspecified"))
      (node (ref "U27") (pin "15") (pinfunction "CAS_15") (pintype "unspecified"))
      (node (ref "U28") (pin "15") (pinfunction "CAS_15") (pintype "unspecified"))
      (node (ref "U29") (pin "15") (pinfunction "CAS_15") (pintype "unspecified"))
      (node (ref "U4") (pin "2") (pinfunction "/CAS_2") (pintype "unspecified"))
    )
    (net (code "31") (name "/CE_CARTRIDGE1") (class "Default")
      (node (ref "DEBUG") (pin "30") (pinfunction "30_30") (pintype "unspecified"))
      (node (ref "U14") (pin "12") (pinfunction "1Y_12") (pintype "unspecified"))
    )
    (net (code "32") (name "/CE_CARTRIDGE2") (class "Default")
      (node (ref "DEBUG") (pin "32") (pinfunction "32_32") (pintype "unspecified"))
      (node (ref "U14") (pin "6") (pinfunction "2Y_6") (pintype "unspecified"))
    )
    (net (code "33") (name "/CE_PIO#") (class "Default")
      (node (ref "U17") (pin "13") (pinfunction "Y2_13") (pintype "unspecified"))
      (node (ref "U2") (pin "4") (pinfunction "/CE_4") (pintype "unspecified"))
    )
    (net (code "34") (name "/CE_ROM_A#") (class "Default")
      (node (ref "DEBUG") (pin "18") (pinfunction "18_18") (pintype "unspecified"))
      (node (ref "U13") (pin "12") (pinfunction "1Y_12") (pintype "unspecified"))
      (node (ref "U5") (pin "20") (pinfunction "CE#_20") (pintype "unspecified"))
    )
    (net (code "35") (name "/CE_ROM_B#") (class "Default")
      (node (ref "DEBUG") (pin "20") (pinfunction "20_20") (pintype "unspecified"))
      (node (ref "U13") (pin "6") (pinfunction "2Y_6") (pintype "unspecified"))
      (node (ref "U6") (pin "20") (pinfunction "CE#_20") (pintype "unspecified"))
    )
    (net (code "36") (name "/CE_ROM_C#") (class "Default")
      (node (ref "DEBUG") (pin "22") (pinfunction "22_22") (pintype "unspecified"))
      (node (ref "U13") (pin "8") (pinfunction "3Y_8") (pintype "unspecified"))
      (node (ref "U8") (pin "20") (pinfunction "CE#_20") (pintype "unspecified"))
    )
    (net (code "37") (name "/CE_ROM_D#") (class "Default")
      (node (ref "DEBUG") (pin "24") (pinfunction "24_24") (pintype "unspecified"))
      (node (ref "U16") (pin "12") (pinfunction "1Y_12") (pintype "unspecified"))
      (node (ref "U7") (pin "20") (pinfunction "CE#_20") (pintype "unspecified"))
    )
    (net (code "38") (name "/CE_SRAM_A#") (class "Default")
      (node (ref "DEBUG") (pin "28") (pinfunction "28_28") (pintype "unspecified"))
      (node (ref "U16") (pin "6") (pinfunction "2Y_6") (pintype "unspecified"))
      (node (ref "U9") (pin "20") (pinfunction "CE#_20") (pintype "unspecified"))
    )
    (net (code "39") (name "/CE_SRAM_B#") (class "Default")
      (node (ref "DEBUG") (pin "26") (pinfunction "26_26") (pintype "unspecified"))
      (node (ref "U10") (pin "20") (pinfunction "CE#_20") (pintype "unspecified"))
      (node (ref "U16") (pin "11") (pinfunction "3C_11") (pintype "unspecified"))
    )
    (net (code "40") (name "/CLK") (class "Default")
      (node (ref "OSC1") (pin "3") (pinfunction "OUTPUT_3") (pintype "unspecified"))
      (node (ref "U1") (pin "6") (pinfunction "CLK_6") (pintype "input"))
      (node (ref "U2") (pin "25") (pinfunction "CLK_25") (pintype "unspecified"))
      (node (ref "U3") (pin "22") (pinfunction "CLOCK_22") (pintype "input"))
    )
    (net (code "41") (name "/COMPOSITE_VIDEO") (class "Default")
      (node (ref "R1") (pin "2") (pinfunction "2_2") (pintype "unspecified"))
      (node (ref "U4") (pin "36") (pinfunction "COMVID_36") (pintype "unspecified"))
      (node (ref "VIDEO/AUDIO") (pin "1") (pinfunction "1_1") (pintype "unspecified"))
    )
    (net (code "42") (name "/CSR#") (class "Default")
      (node (ref "U17") (pin "14") (pinfunction "Y1_14") (pintype "unspecified"))
      (node (ref "U4") (pin "15") (pinfunction "/CSR_15") (pintype "unspecified"))
    )
    (net (code "43") (name "/CSW#") (class "Default")
      (node (ref "U17") (pin "15") (pinfunction "Y0_15") (pintype "unspecified"))
      (node (ref "U4") (pin "14") (pinfunction "/CSW_14") (pintype "unspecified"))
    )
    (net (code "44") (name "/D0") (class "Default")
      (node (ref "DEBUG") (pin "3") (pinfunction "3_3") (pintype "unspecified"))
      (node (ref "U10") (pin "11") (pinfunction "DQ0_11") (pintype "unspecified"))
      (node (ref "U11") (pin "18") (pinfunction "B1_18") (pintype "unspecified"))
      (node (ref "U2") (pin "19") (pinfunction "D0_19") (pintype "unspecified"))
      (node (ref "U3") (pin "37") (pinfunction "DA0_37") (pintype "bidirectional"))
      (node (ref "U4") (pin "17") (pinfunction "CD7_17") (pintype "unspecified"))
      (node (ref "U5") (pin "11") (pinfunction "IO0_11") (pintype "unspecified"))
      (node (ref "U6") (pin "11") (pinfunction "IO0_11") (pintype "unspecified"))
      (node (ref "U7") (pin "11") (pinfunction "IO0_11") (pintype "unspecified"))
      (node (ref "U8") (pin "11") (pinfunction "IO0_11") (pintype "unspecified"))
      (node (ref "U9") (pin "11") (pinfunction "DQ0_11") (pintype "unspecified"))
    )
    (net (code "45") (name "/D1") (class "Default")
      (node (ref "DEBUG") (pin "5") (pinfunction "5_5") (pintype "unspecified"))
      (node (ref "U10") (pin "12") (pinfunction "DQ1_12") (pintype "unspecified"))
      (node (ref "U11") (pin "17") (pinfunction "B2_17") (pintype "unspecified"))
      (node (ref "U2") (pin "20") (pinfunction "D1_20") (pintype "unspecified"))
      (node (ref "U3") (pin "36") (pinfunction "DA1_36") (pintype "bidirectional"))
      (node (ref "U4") (pin "18") (pinfunction "CD6_18") (pintype "unspecified"))
      (node (ref "U5") (pin "12") (pinfunction "IO1_12") (pintype "unspecified"))
      (node (ref "U6") (pin "12") (pinfunction "IO1_12") (pintype "unspecified"))
      (node (ref "U7") (pin "12") (pinfunction "IO1_12") (pintype "unspecified"))
      (node (ref "U8") (pin "12") (pinfunction "IO1_12") (pintype "unspecified"))
      (node (ref "U9") (pin "12") (pinfunction "DQ1_12") (pintype "unspecified"))
    )
    (net (code "46") (name "/D2") (class "Default")
      (node (ref "DEBUG") (pin "7") (pinfunction "7_7") (pintype "unspecified"))
      (node (ref "U10") (pin "13") (pinfunction "QD2_13") (pintype "unspecified"))
      (node (ref "U11") (pin "16") (pinfunction "B3_16") (pintype "unspecified"))
      (node (ref "U2") (pin "1") (pinfunction "D2_1") (pintype "unspecified"))
      (node (ref "U3") (pin "35") (pinfunction "DA2_35") (pintype "bidirectional"))
      (node (ref "U4") (pin "19") (pinfunction "CD5_19") (pintype "unspecified"))
      (node (ref "U5") (pin "13") (pinfunction "IO2_13") (pintype "unspecified"))
      (node (ref "U6") (pin "13") (pinfunction "IO2_13") (pintype "unspecified"))
      (node (ref "U7") (pin "13") (pinfunction "IO2_13") (pintype "unspecified"))
      (node (ref "U8") (pin "13") (pinfunction "IO2_13") (pintype "unspecified"))
      (node (ref "U9") (pin "13") (pinfunction "QD2_13") (pintype "unspecified"))
    )
    (net (code "47") (name "/D3") (class "Default")
      (node (ref "DEBUG") (pin "9") (pinfunction "9_9") (pintype "unspecified"))
      (node (ref "U10") (pin "15") (pinfunction "DQ3_15") (pintype "unspecified"))
      (node (ref "U11") (pin "15") (pinfunction "B4_15") (pintype "unspecified"))
      (node (ref "U2") (pin "40") (pinfunction "D3_40") (pintype "unspecified"))
      (node (ref "U3") (pin "34") (pinfunction "DA3_34") (pintype "bidirectional"))
      (node (ref "U4") (pin "20") (pinfunction "CD4_20") (pintype "unspecified"))
      (node (ref "U5") (pin "15") (pinfunction "IO3_15") (pintype "unspecified"))
      (node (ref "U6") (pin "15") (pinfunction "IO3_15") (pintype "unspecified"))
      (node (ref "U7") (pin "15") (pinfunction "IO3_15") (pintype "unspecified"))
      (node (ref "U8") (pin "15") (pinfunction "IO3_15") (pintype "unspecified"))
      (node (ref "U9") (pin "15") (pinfunction "DQ3_15") (pintype "unspecified"))
    )
    (net (code "48") (name "/D4") (class "Default")
      (node (ref "DEBUG") (pin "11") (pinfunction "11_11") (pintype "unspecified"))
      (node (ref "U10") (pin "16") (pinfunction "DQ4_16") (pintype "unspecified"))
      (node (ref "U11") (pin "14") (pinfunction "B5_14") (pintype "unspecified"))
      (node (ref "U2") (pin "39") (pinfunction "D4_39") (pintype "unspecified"))
      (node (ref "U3") (pin "33") (pinfunction "DA4_33") (pintype "bidirectional"))
      (node (ref "U4") (pin "21") (pinfunction "CD3_21") (pintype "unspecified"))
      (node (ref "U5") (pin "16") (pinfunction "IO4_16") (pintype "unspecified"))
      (node (ref "U6") (pin "16") (pinfunction "IO4_16") (pintype "unspecified"))
      (node (ref "U7") (pin "16") (pinfunction "IO4_16") (pintype "unspecified"))
      (node (ref "U8") (pin "16") (pinfunction "IO4_16") (pintype "unspecified"))
      (node (ref "U9") (pin "16") (pinfunction "DQ4_16") (pintype "unspecified"))
    )
    (net (code "49") (name "/D5") (class "Default")
      (node (ref "DEBUG") (pin "13") (pinfunction "13_13") (pintype "unspecified"))
      (node (ref "U10") (pin "17") (pinfunction "DQ5_17") (pintype "unspecified"))
      (node (ref "U11") (pin "13") (pinfunction "B6_13") (pintype "unspecified"))
      (node (ref "U2") (pin "38") (pinfunction "D5_38") (pintype "unspecified"))
      (node (ref "U3") (pin "32") (pinfunction "DA5_32") (pintype "bidirectional"))
      (node (ref "U4") (pin "22") (pinfunction "CD2_22") (pintype "unspecified"))
      (node (ref "U5") (pin "17") (pinfunction "IO5_17") (pintype "unspecified"))
      (node (ref "U6") (pin "17") (pinfunction "IO5_17") (pintype "unspecified"))
      (node (ref "U7") (pin "17") (pinfunction "IO5_17") (pintype "unspecified"))
      (node (ref "U8") (pin "17") (pinfunction "IO5_17") (pintype "unspecified"))
      (node (ref "U9") (pin "17") (pinfunction "DQ5_17") (pintype "unspecified"))
    )
    (net (code "50") (name "/D6") (class "Default")
      (node (ref "DEBUG") (pin "15") (pinfunction "15_15") (pintype "unspecified"))
      (node (ref "U10") (pin "18") (pinfunction "DQ6_18") (pintype "unspecified"))
      (node (ref "U11") (pin "12") (pinfunction "B7_12") (pintype "unspecified"))
      (node (ref "U2") (pin "3") (pinfunction "D6_3") (pintype "unspecified"))
      (node (ref "U3") (pin "31") (pinfunction "DA6_31") (pintype "bidirectional"))
      (node (ref "U4") (pin "23") (pinfunction "CD1_23") (pintype "unspecified"))
      (node (ref "U5") (pin "18") (pinfunction "IO6_18") (pintype "unspecified"))
      (node (ref "U6") (pin "18") (pinfunction "IO6_18") (pintype "unspecified"))
      (node (ref "U7") (pin "18") (pinfunction "IO6_18") (pintype "unspecified"))
      (node (ref "U8") (pin "18") (pinfunction "IO6_18") (pintype "unspecified"))
      (node (ref "U9") (pin "18") (pinfunction "DQ6_18") (pintype "unspecified"))
    )
    (net (code "51") (name "/D7") (class "Default")
      (node (ref "DEBUG") (pin "17") (pinfunction "17_17") (pintype "unspecified"))
      (node (ref "U10") (pin "19") (pinfunction "DQ7_19") (pintype "unspecified"))
      (node (ref "U11") (pin "11") (pinfunction "B8_11") (pintype "unspecified"))
      (node (ref "U2") (pin "2") (pinfunction "D7_2") (pintype "unspecified"))
      (node (ref "U3") (pin "30") (pinfunction "DA7_30") (pintype "bidirectional"))
      (node (ref "U4") (pin "24") (pinfunction "CD0_24") (pintype "unspecified"))
      (node (ref "U5") (pin "19") (pinfunction "IO7_19") (pintype "unspecified"))
      (node (ref "U6") (pin "19") (pinfunction "IO7_19") (pintype "unspecified"))
      (node (ref "U7") (pin "19") (pinfunction "IO7_19") (pintype "unspecified"))
      (node (ref "U8") (pin "19") (pinfunction "IO7_19") (pintype "unspecified"))
      (node (ref "U9") (pin "19") (pinfunction "DQ7_19") (pintype "unspecified"))
    )
    (net (code "52") (name "/FG") (class "Default")
      (node (ref "AC_CONNECTOR") (pin "2") (pinfunction "2_2") (pintype "unspecified"))
      (node (ref "U19") (pin "3") (pinfunction "FG_3") (pintype "unspecified"))
    )
    (net (code "53") (name "/INT#") (class "Default")
      (node (ref "U1") (pin "16") (pinfunction "INT_16") (pintype "input"))
      (node (ref "U2") (pin "23") (pinfunction "/INT_23") (pintype "unspecified"))
    )
    (net (code "54") (name "/IOOE#") (class "Default")
      (node (ref "U12") (pin "11") (pinfunction "4Y_11") (pintype "unspecified"))
    )
    (net (code "55") (name "/IORQ#") (class "Default")
      (node (ref "U1") (pin "20") (pinfunction "IORQ_20") (pintype "output"))
      (node (ref "U12") (pin "10") (pinfunction "3B_10") (pintype "unspecified"))
      (node (ref "U12") (pin "12") (pinfunction "4A_12") (pintype "unspecified"))
      (node (ref "U17") (pin "4") (pinfunction "G#2A_4") (pintype "unspecified"))
      (node (ref "U2") (pin "36") (pinfunction "/IORQ_36") (pintype "unspecified"))
    )
    (net (code "56") (name "/IOWE#") (class "Default")
      (node (ref "U12") (pin "8") (pinfunction "3Y_8") (pintype "unspecified"))
    )
    (net (code "57") (name "/L") (class "Default")
      (node (ref "AC_CONNECTOR") (pin "1") (pinfunction "1_1") (pintype "unspecified"))
      (node (ref "U19") (pin "1") (pinfunction "L_1") (pintype "unspecified"))
    )
    (net (code "58") (name "/M1#") (class "Default")
      (node (ref "U1") (pin "27") (pinfunction "M1_27") (pintype "output"))
      (node (ref "U2") (pin "37") (pinfunction "/M1_37") (pintype "unspecified"))
    )
    (net (code "59") (name "/MREQ#") (class "Default")
      (node (ref "U1") (pin "19") (pinfunction "MREQ_19") (pintype "output"))
      (node (ref "U12") (pin "2") (pinfunction "1B_2") (pintype "unspecified"))
      (node (ref "U12") (pin "4") (pinfunction "2A_4") (pintype "unspecified"))
    )
    (net (code "60") (name "/N") (class "Default")
      (node (ref "AC_CONNECTOR") (pin "3") (pinfunction "3_3") (pintype "unspecified"))
      (node (ref "U19") (pin "2") (pinfunction "N_2") (pintype "unspecified"))
    )
    (net (code "61") (name "/NA13") (class "Default")
      (node (ref "U13") (pin "11") (pinfunction "3C_11") (pintype "unspecified"))
      (node (ref "U13") (pin "13") (pinfunction "1C_13") (pintype "unspecified"))
      (node (ref "U13") (pin "5") (pinfunction "2C_5") (pintype "unspecified"))
      (node (ref "U15") (pin "6") (pinfunction "3Y_6") (pintype "unspecified"))
      (node (ref "U16") (pin "13") (pinfunction "1C_13") (pintype "unspecified"))
    )
    (net (code "62") (name "/NA14") (class "Default")
      (node (ref "U13") (pin "2") (pinfunction "1B_2") (pintype "unspecified"))
      (node (ref "U13") (pin "4") (pinfunction "2B_4") (pintype "unspecified"))
      (node (ref "U15") (pin "4") (pinfunction "2Y_4") (pintype "unspecified"))
      (node (ref "U16") (pin "4") (pinfunction "2B_4") (pintype "unspecified"))
      (node (ref "U16") (pin "9") (pinfunction "3A_9") (pintype "unspecified"))
    )
    (net (code "63") (name "/NA15") (class "Default")
      (node (ref "U13") (pin "1") (pinfunction "1A_1") (pintype "unspecified"))
      (node (ref "U13") (pin "9") (pinfunction "3A_9") (pintype "unspecified"))
      (node (ref "U14") (pin "1") (pinfunction "1A_1") (pintype "unspecified"))
      (node (ref "U15") (pin "2") (pinfunction "1Y_2") (pintype "unspecified"))
      (node (ref "U16") (pin "3") (pinfunction "2A_3") (pintype "unspecified"))
    )
    (net (code "64") (name "/NMI#") (class "Default")
      (node (ref "U1") (pin "17") (pinfunction "NMI_17") (pintype "input"))
      (node (ref "U4") (pin "16") (pinfunction "/INT_16") (pintype "unspecified"))
    )
    (net (code "65") (name "/NWR#") (class "Default")
      (node (ref "U11") (pin "1") (pinfunction "DIR_1") (pintype "unspecified"))
      (node (ref "U15") (pin "8") (pinfunction "4Y_8") (pintype "unspecified"))
    )
    (net (code "66") (name "/OE#") (class "Default")
      (node (ref "U10") (pin "22") (pinfunction "OE#_22") (pintype "unspecified"))
      (node (ref "U12") (pin "6") (pinfunction "2Y_6") (pintype "unspecified"))
      (node (ref "U5") (pin "22") (pinfunction "OE#_22") (pintype "unspecified"))
      (node (ref "U6") (pin "22") (pinfunction "OE#_22") (pintype "unspecified"))
      (node (ref "U7") (pin "22") (pinfunction "OE#_22") (pintype "unspecified"))
      (node (ref "U8") (pin "22") (pinfunction "OE#_22") (pintype "unspecified"))
      (node (ref "U9") (pin "22") (pinfunction "OE#_22") (pintype "unspecified"))
    )
    (net (code "67") (name "/RAS#") (class "Default")
      (node (ref "U22") (pin "4") (pinfunction "RAS_4") (pintype "unspecified"))
      (node (ref "U23") (pin "4") (pinfunction "RAS_4") (pintype "unspecified"))
      (node (ref "U24") (pin "4") (pinfunction "RAS_4") (pintype "unspecified"))
      (node (ref "U25") (pin "4") (pinfunction "RAS_4") (pintype "unspecified"))
      (node (ref "U26") (pin "4") (pinfunction "RAS_4") (pintype "unspecified"))
      (node (ref "U27") (pin "4") (pinfunction "RAS_4") (pintype "unspecified"))
      (node (ref "U28") (pin "4") (pinfunction "RAS_4") (pintype "unspecified"))
      (node (ref "U29") (pin "4") (pinfunction "RAS_4") (pintype "unspecified"))
      (node (ref "U4") (pin "1") (pinfunction "/RAS_1") (pintype "unspecified"))
    )
    (net (code "68") (name "/RD#") (class "Default")
      (node (ref "U1") (pin "21") (pinfunction "RD_21") (pintype "output"))
      (node (ref "U12") (pin "13") (pinfunction "4B_13") (pintype "unspecified"))
      (node (ref "U12") (pin "5") (pinfunction "2B_5") (pintype "unspecified"))
      (node (ref "U2") (pin "35") (pinfunction "RD_35") (pintype "unspecified"))
    )
    (net (code "69") (name "/RD0") (class "Default")
      (node (ref "U22") (pin "14") (pinfunction "DOUT_14") (pintype "unspecified"))
      (node (ref "U4") (pin "32") (pinfunction "RD0_32") (pintype "unspecified"))
    )
    (net (code "70") (name "/RD1") (class "Default")
      (node (ref "U23") (pin "14") (pinfunction "DOUT_14") (pintype "unspecified"))
      (node (ref "U4") (pin "31") (pinfunction "RD1_31") (pintype "unspecified"))
    )
    (net (code "71") (name "/RD2") (class "Default")
      (node (ref "U24") (pin "14") (pinfunction "DOUT_14") (pintype "unspecified"))
      (node (ref "U4") (pin "30") (pinfunction "RD2_30") (pintype "unspecified"))
    )
    (net (code "72") (name "/RD3") (class "Default")
      (node (ref "U25") (pin "14") (pinfunction "DOUT_14") (pintype "unspecified"))
      (node (ref "U4") (pin "29") (pinfunction "RD3_29") (pintype "unspecified"))
    )
    (net (code "73") (name "/RD4") (class "Default")
      (node (ref "U26") (pin "14") (pinfunction "DOUT_14") (pintype "unspecified"))
      (node (ref "U4") (pin "28") (pinfunction "RD4_28") (pintype "unspecified"))
    )
    (net (code "74") (name "/RD5") (class "Default")
      (node (ref "U27") (pin "14") (pinfunction "DOUT_14") (pintype "unspecified"))
      (node (ref "U4") (pin "27") (pinfunction "RD5_27") (pintype "unspecified"))
    )
    (net (code "75") (name "/RD6") (class "Default")
      (node (ref "U28") (pin "14") (pinfunction "DOUT_14") (pintype "unspecified"))
      (node (ref "U4") (pin "26") (pinfunction "RD6_26") (pintype "unspecified"))
    )
    (net (code "76") (name "/RD7") (class "Default")
      (node (ref "U29") (pin "14") (pinfunction "DOUT_14") (pintype "unspecified"))
      (node (ref "U4") (pin "25") (pinfunction "RD7_25") (pintype "unspecified"))
    )
    (net (code "77") (name "/RESET#") (class "Default")
      (node (ref "KEYBOARD_CONNECTOR") (pin "16") (pinfunction "16_16") (pintype "unspecified"))
      (node (ref "U1") (pin "26") (pinfunction "RESET_26") (pintype "input"))
      (node (ref "U3") (pin "23") (pinfunction "RESET_23") (pintype "input"))
      (node (ref "U4") (pin "34") (pinfunction "/RESET/SYNC_34") (pintype "unspecified"))
    )
    (net (code "78") (name "/R{slash}W") (class "Default")
      (node (ref "U22") (pin "3") (pinfunction "WE_3") (pintype "unspecified"))
      (node (ref "U23") (pin "3") (pinfunction "WE_3") (pintype "unspecified"))
      (node (ref "U24") (pin "3") (pinfunction "WE_3") (pintype "unspecified"))
      (node (ref "U25") (pin "3") (pinfunction "WE_3") (pintype "unspecified"))
      (node (ref "U26") (pin "3") (pinfunction "WE_3") (pintype "unspecified"))
      (node (ref "U27") (pin "3") (pinfunction "WE_3") (pintype "unspecified"))
      (node (ref "U28") (pin "3") (pinfunction "WE_3") (pintype "unspecified"))
      (node (ref "U29") (pin "3") (pinfunction "WE_3") (pintype "unspecified"))
      (node (ref "U4") (pin "11") (pinfunction "R//W_11") (pintype "unspecified"))
    )
    (net (code "79") (name "/WE#") (class "Default")
      (node (ref "U10") (pin "27") (pinfunction "WE#_27") (pintype "unspecified"))
      (node (ref "U12") (pin "3") (pinfunction "1Y_3") (pintype "unspecified"))
      (node (ref "U5") (pin "27") (pinfunction "WE#_27") (pintype "unspecified"))
      (node (ref "U6") (pin "27") (pinfunction "WE#_27") (pintype "unspecified"))
      (node (ref "U7") (pin "27") (pinfunction "WE#_27") (pintype "unspecified"))
      (node (ref "U8") (pin "27") (pinfunction "WE#_27") (pintype "unspecified"))
      (node (ref "U9") (pin "27") (pinfunction "WE#_27") (pintype "unspecified"))
    )
    (net (code "80") (name "/WR#") (class "Default")
      (node (ref "U1") (pin "22") (pinfunction "WR_22") (pintype "output"))
      (node (ref "U12") (pin "1") (pinfunction "1A_1") (pintype "unspecified"))
      (node (ref "U12") (pin "9") (pinfunction "3A_9") (pintype "unspecified"))
      (node (ref "U15") (pin "9") (pinfunction "4A_9") (pintype "unspecified"))
    )
    (net (code "81") (name "COL1") (class "Default")
      (node (ref "KEYBOARD_CONNECTOR") (pin "19") (pinfunction "19_19") (pintype "unspecified"))
      (node (ref "U2") (pin "27") (pinfunction "PB0_27") (pintype "unspecified"))
    )
    (net (code "82") (name "COL2") (class "Default")
      (node (ref "KEYBOARD_CONNECTOR") (pin "14") (pinfunction "14_14") (pintype "unspecified"))
      (node (ref "U2") (pin "28") (pinfunction "PB1_28") (pintype "unspecified"))
    )
    (net (code "83") (name "COL3") (class "Default")
      (node (ref "KEYBOARD_CONNECTOR") (pin "12") (pinfunction "12_12") (pintype "unspecified"))
      (node (ref "U2") (pin "29") (pinfunction "PB2_29") (pintype "unspecified"))
    )
    (net (code "84") (name "COL4") (class "Default")
      (node (ref "KEYBOARD_CONNECTOR") (pin "10") (pinfunction "10_10") (pintype "unspecified"))
      (node (ref "U2") (pin "30") (pinfunction "PB3_30") (pintype "unspecified"))
    )
    (net (code "85") (name "COL5") (class "Default")
      (node (ref "KEYBOARD_CONNECTOR") (pin "8") (pinfunction "8_8") (pintype "unspecified"))
      (node (ref "U2") (pin "31") (pinfunction "PB4_31") (pintype "unspecified"))
    )
    (net (code "86") (name "COL6") (class "Default")
      (node (ref "KEYBOARD_CONNECTOR") (pin "6") (pinfunction "6_6") (pintype "unspecified"))
      (node (ref "U2") (pin "32") (pinfunction "PB5_32") (pintype "unspecified"))
    )
    (net (code "87") (name "COL7") (class "Default")
      (node (ref "KEYBOARD_CONNECTOR") (pin "4") (pinfunction "4_4") (pintype "unspecified"))
      (node (ref "U2") (pin "33") (pinfunction "PB6_33") (pintype "unspecified"))
    )
    (net (code "88") (name "COL8") (class "Default")
      (node (ref "KEYBOARD_CONNECTOR") (pin "2") (pinfunction "2_2") (pintype "unspecified"))
      (node (ref "U2") (pin "34") (pinfunction "PB7_34") (pintype "unspecified"))
    )
    (net (code "89") (name "GND") (class "Default")
      (node (ref "C1") (pin "1") (pinfunction "1_1") (pintype "unspecified"))
      (node (ref "C10") (pin "1") (pinfunction "1_1") (pintype "unspecified"))
      (node (ref "C11") (pin "1") (pinfunction "1_1") (pintype "unspecified"))
      (node (ref "C12") (pin "1") (pinfunction "1_1") (pintype "unspecified"))
      (node (ref "C13") (pin "1") (pinfunction "1_1") (pintype "unspecified"))
      (node (ref "C14") (pin "1") (pinfunction "1_1") (pintype "unspecified"))
      (node (ref "C15") (pin "1") (pinfunction "1_1") (pintype "unspecified"))
      (node (ref "C16") (pin "1") (pinfunction "1_1") (pintype "unspecified"))
      (node (ref "C17") (pin "1") (pinfunction "1_1") (pintype "unspecified"))
      (node (ref "C18") (pin "1") (pinfunction "1_1") (pintype "unspecified"))
      (node (ref "C19") (pin "1") (pinfunction "1_1") (pintype "unspecified"))
      (node (ref "C2") (pin "1") (pinfunction "1_1") (pintype "unspecified"))
      (node (ref "C20") (pin "1") (pinfunction "1_1") (pintype "unspecified"))
      (node (ref "C21") (pin "1") (pinfunction "1_1") (pintype "unspecified"))
      (node (ref "C22") (pin "1") (pinfunction "1_1") (pintype "unspecified"))
      (node (ref "C23") (pin "1") (pinfunction "1_1") (pintype "unspecified"))
      (node (ref "C24") (pin "1") (pinfunction "1_1") (pintype "unspecified"))
      (node (ref "C25") (pin "1") (pinfunction "1_1") (pintype "unspecified"))
      (node (ref "C26") (pin "1") (pinfunction "1_1") (pintype "unspecified"))
      (node (ref "C27") (pin "1") (pinfunction "1_1") (pintype "unspecified"))
      (node (ref "C28") (pin "1") (pinfunction "1_1") (pintype "unspecified"))
      (node (ref "C29") (pin "1") (pinfunction "1_1") (pintype "unspecified"))
      (node (ref "C3") (pin "2") (pinfunction "2_2") (pintype "input"))
      (node (ref "C4") (pin "1") (pinfunction "1_1") (pintype "unspecified"))
      (node (ref "C5") (pin "1") (pinfunction "1_1") (pintype "unspecified"))
      (node (ref "C6") (pin "1") (pinfunction "1_1") (pintype "unspecified"))
      (node (ref "C7") (pin "1") (pinfunction "1_1") (pintype "unspecified"))
      (node (ref "C8") (pin "1") (pinfunction "1_1") (pintype "unspecified"))
      (node (ref "C9") (pin "1") (pinfunction "1_1") (pintype "unspecified"))
      (node (ref "DEBUG") (pin "34") (pinfunction "34_34") (pintype "unspecified"))
      (node (ref "H2") (pin "2") (pinfunction "2_2") (pintype "unspecified"))
      (node (ref "J1") (pin "2") (pinfunction "2_2") (pintype "unspecified"))
      (node (ref "KEYBOARD_CONNECTOR") (pin "18") (pinfunction "18_18") (pintype "unspecified"))
      (node (ref "KEYBOARD_CONNECTOR") (pin "20") (pinfunction "20_20") (pintype "unspecified"))
      (node (ref "OSC1") (pin "2") (pinfunction "GND_2") (pintype "unspecified"))
      (node (ref "R1") (pin "1") (pinfunction "1_1") (pintype "unspecified"))
      (node (ref "R7") (pin "1") (pinfunction "1_1") (pintype "unspecified"))
      (node (ref "SPK1") (pin "2") (pinfunction "-_2") (pintype "unspecified"))
      (node (ref "U1") (pin "29") (pinfunction "GND_29") (pintype "bidirectional"))
      (node (ref "U10") (pin "1") (pinfunction "A14_1") (pintype "unspecified"))
      (node (ref "U10") (pin "14") (pinfunction "VSS_14") (pintype "unspecified"))
      (node (ref "U10") (pin "26") (pinfunction "A13_26") (pintype "unspecified"))
      (node (ref "U11") (pin "10") (pinfunction "GND_10") (pintype "unspecified"))
      (node (ref "U11") (pin "19") (pinfunction "OE#_19") (pintype "unspecified"))
      (node (ref "U12") (pin "7") (pinfunction "GND_7") (pintype "unspecified"))
      (node (ref "U13") (pin "7") (pinfunction "GND_7") (pintype "unspecified"))
      (node (ref "U14") (pin "7") (pinfunction "GND_7") (pintype "unspecified"))
      (node (ref "U15") (pin "7") (pinfunction "GND_7") (pintype "unspecified"))
      (node (ref "U16") (pin "7") (pinfunction "GND_7") (pintype "unspecified"))
      (node (ref "U17") (pin "5") (pinfunction "G#2B_5") (pintype "unspecified"))
      (node (ref "U17") (pin "8") (pinfunction "GND_8") (pintype "unspecified"))
      (node (ref "U18") (pin "7") (pinfunction "GND_7") (pintype "unspecified"))
      (node (ref "U19") (pin "5") (pinfunction "Vo-_5") (pintype "unspecified"))
      (node (ref "U2") (pin "11") (pinfunction "GND_11") (pintype "unspecified"))
      (node (ref "U2") (pin "24") (pinfunction "IEI_24") (pintype "unspecified"))
      (node (ref "U20") (pin "2") (pinfunction "GND_2") (pintype "unspecified"))
      (node (ref "U21") (pin "2") (pinfunction "GND_2") (pintype "passive"))
      (node (ref "U22") (pin "16") (pinfunction "VSS_16") (pintype "unspecified"))
      (node (ref "U23") (pin "16") (pinfunction "VSS_16") (pintype "unspecified"))
      (node (ref "U24") (pin "16") (pinfunction "VSS_16") (pintype "unspecified"))
      (node (ref "U25") (pin "16") (pinfunction "VSS_16") (pintype "unspecified"))
      (node (ref "U26") (pin "16") (pinfunction "VSS_16") (pintype "unspecified"))
      (node (ref "U27") (pin "16") (pinfunction "VSS_16") (pintype "unspecified"))
      (node (ref "U28") (pin "16") (pinfunction "VSS_16") (pintype "unspecified"))
      (node (ref "U29") (pin "16") (pinfunction "VSS_16") (pintype "unspecified"))
      (node (ref "U3") (pin "1") (pinfunction "GND_1") (pintype "bidirectional"))
      (node (ref "U3") (pin "25") (pinfunction "A8_25") (pintype "input"))
      (node (ref "U3") (pin "26") (pinfunction "SEL_26") (pintype "input"))
      (node (ref "U4") (pin "12") (pinfunction "GND_12") (pintype "unspecified"))
      (node (ref "U5") (pin "14") (pinfunction "GND_14") (pintype "unspecified"))
      (node (ref "U6") (pin "14") (pinfunction "GND_14") (pintype "unspecified"))
      (node (ref "U7") (pin "14") (pinfunction "GND_14") (pintype "unspecified"))
      (node (ref "U8") (pin "14") (pinfunction "GND_14") (pintype "unspecified"))
      (node (ref "U9") (pin "1") (pinfunction "A14_1") (pintype "unspecified"))
      (node (ref "U9") (pin "14") (pinfunction "VSS_14") (pintype "unspecified"))
      (node (ref "U9") (pin "26") (pinfunction "A13_26") (pintype "unspecified"))
      (node (ref "VIDEO/AUDIO") (pin "2") (pinfunction "2_2") (pintype "unspecified"))
      (node (ref "YM2612_IO_PORT") (pin "18") (pinfunction "18_18") (pintype "unspecified"))
    )
    (net (code "90") (name "Net-(OSC2-OSC1)") (class "Default")
      (node (ref "C1") (pin "2") (pinfunction "2_2") (pintype "unspecified"))
      (node (ref "OSC2") (pin "1") (pinfunction "OSC1_1") (pintype "input"))
      (node (ref "U4") (pin "39") (pinfunction "XTAL1_39") (pintype "unspecified"))
    )
    (net (code "91") (name "Net-(OSC2-OSC2)") (class "Default")
      (node (ref "C2") (pin "2") (pinfunction "2_2") (pintype "unspecified"))
      (node (ref "OSC2") (pin "2") (pinfunction "OSC2_2") (pintype "input"))
      (node (ref "U4") (pin "40") (pinfunction "XTAL2_40") (pintype "unspecified"))
    )
    (net (code "92") (name "Net-(U1-BUSRQ)") (class "Default")
      (node (ref "R9") (pin "2") (pinfunction "2_2") (pintype "unspecified"))
      (node (ref "U1") (pin "25") (pinfunction "BUSRQ_25") (pintype "input"))
    )
    (net (code "93") (name "Net-(U1-D0)") (class "Default")
      (node (ref "U1") (pin "14") (pinfunction "D0_14") (pintype "bidirectional"))
      (node (ref "U11") (pin "2") (pinfunction "A1_2") (pintype "unspecified"))
    )
    (net (code "94") (name "Net-(U1-D1)") (class "Default")
      (node (ref "U1") (pin "15") (pinfunction "D1_15") (pintype "bidirectional"))
      (node (ref "U11") (pin "3") (pinfunction "A2_3") (pintype "unspecified"))
    )
    (net (code "95") (name "Net-(U1-D2)") (class "Default")
      (node (ref "U1") (pin "12") (pinfunction "D2_12") (pintype "bidirectional"))
      (node (ref "U11") (pin "4") (pinfunction "A3_4") (pintype "unspecified"))
    )
    (net (code "96") (name "Net-(U1-D3)") (class "Default")
      (node (ref "U1") (pin "8") (pinfunction "D3_8") (pintype "bidirectional"))
      (node (ref "U11") (pin "5") (pinfunction "A4_5") (pintype "unspecified"))
    )
    (net (code "97") (name "Net-(U1-D4)") (class "Default")
      (node (ref "U1") (pin "7") (pinfunction "D4_7") (pintype "bidirectional"))
      (node (ref "U11") (pin "6") (pinfunction "A5_6") (pintype "unspecified"))
    )
    (net (code "98") (name "Net-(U1-D5)") (class "Default")
      (node (ref "U1") (pin "9") (pinfunction "D5_9") (pintype "bidirectional"))
      (node (ref "U11") (pin "7") (pinfunction "A6_7") (pintype "unspecified"))
    )
    (net (code "99") (name "Net-(U1-D6)") (class "Default")
      (node (ref "U1") (pin "10") (pinfunction "D6_10") (pintype "bidirectional"))
      (node (ref "U11") (pin "8") (pinfunction "A7_8") (pintype "unspecified"))
    )
    (net (code "100") (name "Net-(U1-D7)") (class "Default")
      (node (ref "U1") (pin "13") (pinfunction "D7_13") (pintype "bidirectional"))
      (node (ref "U11") (pin "9") (pinfunction "A8_9") (pintype "unspecified"))
    )
    (net (code "101") (name "Net-(U1-WAIT)") (class "Default")
      (node (ref "R8") (pin "2") (pinfunction "2_2") (pintype "unspecified"))
      (node (ref "U1") (pin "24") (pinfunction "WAIT_24") (pintype "input"))
    )
    (net (code "102") (name "Net-(U2-{slash}ASTB)") (class "Default")
      (node (ref "R10") (pin "2") (pinfunction "2_2") (pintype "unspecified"))
      (node (ref "U2") (pin "16") (pinfunction "/ASTB_16") (pintype "unspecified"))
    )
    (net (code "103") (name "Net-(U2-{slash}BSTB)") (class "Default")
      (node (ref "R11") (pin "2") (pinfunction "2_2") (pintype "unspecified"))
      (node (ref "U2") (pin "17") (pinfunction "/BSTB_17") (pintype "unspecified"))
    )
    (net (code "104") (name "Net-(U3-ACA)") (class "Default")
      (node (ref "R2") (pin "1") (pinfunction "1_1") (pintype "unspecified"))
      (node (ref "U3") (pin "3") (pinfunction "ACA_3") (pintype "unspecified"))
    )
    (net (code "105") (name "Net-(U3-ACB)") (class "Default")
      (node (ref "R3") (pin "1") (pinfunction "1_1") (pintype "unspecified"))
      (node (ref "U3") (pin "4") (pinfunction "ACB_4") (pintype "unspecified"))
    )
    (net (code "106") (name "Net-(U3-ACC)") (class "Default")
      (node (ref "R4") (pin "1") (pinfunction "1_1") (pintype "unspecified"))
      (node (ref "U3") (pin "38") (pinfunction "ACC_38") (pintype "unspecified"))
    )
    (net (code "107") (name "Net-(U3-IOA0)") (class "Default")
      (node (ref "U3") (pin "21") (pinfunction "IOA0_21") (pintype "bidirectional"))
      (node (ref "YM2612_IO_PORT") (pin "2") (pinfunction "2_2") (pintype "unspecified"))
    )
    (net (code "108") (name "Net-(U3-IOA1)") (class "Default")
      (node (ref "U3") (pin "20") (pinfunction "IOA1_20") (pintype "bidirectional"))
      (node (ref "YM2612_IO_PORT") (pin "4") (pinfunction "4_4") (pintype "unspecified"))
    )
    (net (code "109") (name "Net-(U3-IOA2)") (class "Default")
      (node (ref "U3") (pin "19") (pinfunction "IOA2_19") (pintype "bidirectional"))
      (node (ref "YM2612_IO_PORT") (pin "6") (pinfunction "6_6") (pintype "unspecified"))
    )
    (net (code "110") (name "Net-(U3-IOA3)") (class "Default")
      (node (ref "U3") (pin "18") (pinfunction "IOA3_18") (pintype "bidirectional"))
      (node (ref "YM2612_IO_PORT") (pin "8") (pinfunction "8_8") (pintype "unspecified"))
    )
    (net (code "111") (name "Net-(U3-IOA4)") (class "Default")
      (node (ref "U3") (pin "17") (pinfunction "IOA4_17") (pintype "bidirectional"))
      (node (ref "YM2612_IO_PORT") (pin "10") (pinfunction "10_10") (pintype "unspecified"))
    )
    (net (code "112") (name "Net-(U3-IOA5)") (class "Default")
      (node (ref "U3") (pin "16") (pinfunction "IOA5_16") (pintype "bidirectional"))
      (node (ref "YM2612_IO_PORT") (pin "12") (pinfunction "12_12") (pintype "unspecified"))
    )
    (net (code "113") (name "Net-(U3-IOA6)") (class "Default")
      (node (ref "U3") (pin "15") (pinfunction "IOA6_15") (pintype "bidirectional"))
      (node (ref "YM2612_IO_PORT") (pin "14") (pinfunction "14_14") (pintype "unspecified"))
    )
    (net (code "114") (name "Net-(U3-IOA7)") (class "Default")
      (node (ref "U3") (pin "14") (pinfunction "IOA7_14") (pintype "bidirectional"))
      (node (ref "YM2612_IO_PORT") (pin "16") (pinfunction "16_16") (pintype "unspecified"))
    )
    (net (code "115") (name "Net-(U3-IOB0)") (class "Default")
      (node (ref "U3") (pin "13") (pinfunction "IOB0_13") (pintype "bidirectional"))
      (node (ref "YM2612_IO_PORT") (pin "3") (pinfunction "3_3") (pintype "unspecified"))
    )
    (net (code "116") (name "Net-(U3-IOB1)") (class "Default")
      (node (ref "U3") (pin "12") (pinfunction "IOB1_12") (pintype "bidirectional"))
      (node (ref "YM2612_IO_PORT") (pin "5") (pinfunction "5_5") (pintype "unspecified"))
    )
    (net (code "117") (name "Net-(U3-IOB2)") (class "Default")
      (node (ref "U3") (pin "11") (pinfunction "IOB2_11") (pintype "bidirectional"))
      (node (ref "YM2612_IO_PORT") (pin "7") (pinfunction "7_7") (pintype "unspecified"))
    )
    (net (code "118") (name "Net-(U3-IOB3)") (class "Default")
      (node (ref "U3") (pin "10") (pinfunction "IOB3_10") (pintype "bidirectional"))
      (node (ref "YM2612_IO_PORT") (pin "9") (pinfunction "9_9") (pintype "unspecified"))
    )
    (net (code "119") (name "Net-(U3-IOB4)") (class "Default")
      (node (ref "U3") (pin "9") (pinfunction "IOB4_9") (pintype "bidirectional"))
      (node (ref "YM2612_IO_PORT") (pin "11") (pinfunction "11_11") (pintype "unspecified"))
    )
    (net (code "120") (name "Net-(U3-IOB5)") (class "Default")
      (node (ref "U3") (pin "8") (pinfunction "IOB5_8") (pintype "bidirectional"))
      (node (ref "YM2612_IO_PORT") (pin "13") (pinfunction "13_13") (pintype "unspecified"))
    )
    (net (code "121") (name "Net-(U3-IOB6)") (class "Default")
      (node (ref "U3") (pin "7") (pinfunction "IOB6_7") (pintype "bidirectional"))
      (node (ref "YM2612_IO_PORT") (pin "15") (pinfunction "15_15") (pintype "unspecified"))
    )
    (net (code "122") (name "Net-(U3-IOB7)") (class "Default")
      (node (ref "U3") (pin "6") (pinfunction "IOB7_6") (pintype "bidirectional"))
      (node (ref "YM2612_IO_PORT") (pin "17") (pinfunction "17_17") (pintype "unspecified"))
    )
    (net (code "123") (name "Net-(U17-Y3)") (class "Default")
      (node (ref "U17") (pin "12") (pinfunction "Y3_12") (pintype "unspecified"))
      (node (ref "U18") (pin "1") (pinfunction "1A_1") (pintype "unspecified"))
      (node (ref "U18") (pin "4") (pinfunction "2A_4") (pintype "unspecified"))
    )
    (net (code "124") (name "Net-(U17-Y4)") (class "Default")
      (node (ref "U17") (pin "11") (pinfunction "Y4_11") (pintype "unspecified"))
      (node (ref "U18") (pin "2") (pinfunction "1B_2") (pintype "unspecified"))
    )
    (net (code "125") (name "Net-(U17-Y5)") (class "Default")
      (node (ref "U17") (pin "10") (pinfunction "Y5_10") (pintype "unspecified"))
      (node (ref "U18") (pin "5") (pinfunction "2B_5") (pintype "unspecified"))
    )
    (net (code "126") (name "Net-(U19-Vo+)") (class "Default")
      (node (ref "ON/OFF") (pin "2") (pinfunction "2_2") (pintype "unspecified"))
      (node (ref "U19") (pin "9") (pinfunction "Vo+_9") (pintype "unspecified"))
    )
    (net (code "127") (name "ROW1") (class "Default")
      (node (ref "KEYBOARD_CONNECTOR") (pin "3") (pinfunction "3_3") (pintype "unspecified"))
      (node (ref "U2") (pin "15") (pinfunction "PA0_15") (pintype "unspecified"))
    )
    (net (code "128") (name "ROW2") (class "Default")
      (node (ref "KEYBOARD_CONNECTOR") (pin "5") (pinfunction "5_5") (pintype "unspecified"))
      (node (ref "U2") (pin "14") (pinfunction "PA1_14") (pintype "unspecified"))
    )
    (net (code "129") (name "ROW3") (class "Default")
      (node (ref "KEYBOARD_CONNECTOR") (pin "7") (pinfunction "7_7") (pintype "unspecified"))
      (node (ref "U2") (pin "13") (pinfunction "PA2_13") (pintype "unspecified"))
    )
    (net (code "130") (name "ROW4") (class "Default")
      (node (ref "KEYBOARD_CONNECTOR") (pin "9") (pinfunction "9_9") (pintype "unspecified"))
      (node (ref "U2") (pin "12") (pinfunction "PA3_12") (pintype "unspecified"))
    )
    (net (code "131") (name "ROW5") (class "Default")
      (node (ref "KEYBOARD_CONNECTOR") (pin "11") (pinfunction "11_11") (pintype "unspecified"))
      (node (ref "U2") (pin "10") (pinfunction "PA4_10") (pintype "unspecified"))
    )
    (net (code "132") (name "ROW6") (class "Default")
      (node (ref "KEYBOARD_CONNECTOR") (pin "13") (pinfunction "13_13") (pintype "unspecified"))
      (node (ref "U2") (pin "9") (pinfunction "PA5_9") (pintype "unspecified"))
    )
    (net (code "133") (name "ROW7") (class "Default")
      (node (ref "KEYBOARD_CONNECTOR") (pin "15") (pinfunction "15_15") (pintype "unspecified"))
      (node (ref "U2") (pin "8") (pinfunction "PA6_8") (pintype "unspecified"))
    )
    (net (code "134") (name "ROW8") (class "Default")
      (node (ref "KEYBOARD_CONNECTOR") (pin "17") (pinfunction "17_17") (pintype "unspecified"))
      (node (ref "U2") (pin "7") (pinfunction "PA7_7") (pintype "unspecified"))
    )
    (net (code "135") (name "VCC") (class "Default")
      (node (ref "C10") (pin "2") (pinfunction "2_2") (pintype "unspecified"))
      (node (ref "C11") (pin "2") (pinfunction "2_2") (pintype "unspecified"))
      (node (ref "C12") (pin "2") (pinfunction "2_2") (pintype "unspecified"))
      (node (ref "C13") (pin "2") (pinfunction "2_2") (pintype "unspecified"))
      (node (ref "C14") (pin "2") (pinfunction "2_2") (pintype "unspecified"))
      (node (ref "C15") (pin "2") (pinfunction "2_2") (pintype "unspecified"))
      (node (ref "C16") (pin "2") (pinfunction "2_2") (pintype "unspecified"))
      (node (ref "C17") (pin "2") (pinfunction "2_2") (pintype "unspecified"))
      (node (ref "C18") (pin "2") (pinfunction "2_2") (pintype "unspecified"))
      (node (ref "C19") (pin "2") (pinfunction "2_2") (pintype "unspecified"))
      (node (ref "C20") (pin "2") (pinfunction "2_2") (pintype "unspecified"))
      (node (ref "C21") (pin "2") (pinfunction "2_2") (pintype "unspecified"))
      (node (ref "C22") (pin "2") (pinfunction "2_2") (pintype "unspecified"))
      (node (ref "C23") (pin "2") (pinfunction "2_2") (pintype "unspecified"))
      (node (ref "C24") (pin "2") (pinfunction "2_2") (pintype "unspecified"))
      (node (ref "C25") (pin "2") (pinfunction "2_2") (pintype "unspecified"))
      (node (ref "C26") (pin "2") (pinfunction "2_2") (pintype "unspecified"))
      (node (ref "C27") (pin "2") (pinfunction "2_2") (pintype "unspecified"))
      (node (ref "C28") (pin "2") (pinfunction "2_2") (pintype "unspecified"))
      (node (ref "C29") (pin "2") (pinfunction "2_2") (pintype "unspecified"))
      (node (ref "C4") (pin "2") (pinfunction "2_2") (pintype "unspecified"))
      (node (ref "C5") (pin "2") (pinfunction "2_2") (pintype "unspecified"))
      (node (ref "C6") (pin "2") (pinfunction "2_2") (pintype "unspecified"))
      (node (ref "C7") (pin "2") (pinfunction "2_2") (pintype "unspecified"))
      (node (ref "C8") (pin "2") (pinfunction "2_2") (pintype "unspecified"))
      (node (ref "C9") (pin "2") (pinfunction "2_2") (pintype "unspecified"))
      (node (ref "DEBUG") (pin "1") (pinfunction "1_1") (pintype "unspecified"))
      (node (ref "H2") (pin "1") (pinfunction "1_1") (pintype "unspecified"))
      (node (ref "J1") (pin "1") (pinfunction "1_1") (pintype "unspecified"))
      (node (ref "KEYBOARD_CONNECTOR") (pin "1") (pinfunction "1_1") (pintype "unspecified"))
      (node (ref "OSC1") (pin "4") (pinfunction "VDD_4") (pintype "unspecified"))
      (node (ref "R10") (pin "1") (pinfunction "1_1") (pintype "unspecified"))
      (node (ref "R11") (pin "1") (pinfunction "1_1") (pintype "unspecified"))
      (node (ref "R8") (pin "1") (pinfunction "1_1") (pintype "unspecified"))
      (node (ref "R9") (pin "1") (pinfunction "1_1") (pintype "unspecified"))
      (node (ref "U1") (pin "11") (pinfunction "VCC_11") (pintype "bidirectional"))
      (node (ref "U10") (pin "28") (pinfunction "VCC_28") (pintype "unspecified"))
      (node (ref "U11") (pin "20") (pinfunction "VCC_20") (pintype "unspecified"))
      (node (ref "U12") (pin "14") (pinfunction "VCC_14") (pintype "unspecified"))
      (node (ref "U13") (pin "14") (pinfunction "VCC_14") (pintype "unspecified"))
      (node (ref "U14") (pin "14") (pinfunction "VCC_14") (pintype "unspecified"))
      (node (ref "U15") (pin "14") (pinfunction "VCC_14") (pintype "unspecified"))
      (node (ref "U16") (pin "14") (pinfunction "VCC_14") (pintype "unspecified"))
      (node (ref "U17") (pin "16") (pinfunction "VCC_16") (pintype "unspecified"))
      (node (ref "U17") (pin "6") (pinfunction "G1_6") (pintype "unspecified"))
      (node (ref "U18") (pin "14") (pinfunction "VCC_14") (pintype "unspecified"))
      (node (ref "U2") (pin "26") (pinfunction "5V_26") (pintype "unspecified"))
      (node (ref "U21") (pin "3") (pinfunction "OUT_3") (pintype "passive"))
      (node (ref "U22") (pin "9") (pinfunction "VCC_9") (pintype "unspecified"))
      (node (ref "U23") (pin "9") (pinfunction "VCC_9") (pintype "unspecified"))
      (node (ref "U24") (pin "9") (pinfunction "VCC_9") (pintype "unspecified"))
      (node (ref "U25") (pin "9") (pinfunction "VCC_9") (pintype "unspecified"))
      (node (ref "U26") (pin "9") (pinfunction "VCC_9") (pintype "unspecified"))
      (node (ref "U27") (pin "9") (pinfunction "VCC_9") (pintype "unspecified"))
      (node (ref "U28") (pin "9") (pinfunction "VCC_9") (pintype "unspecified"))
      (node (ref "U29") (pin "9") (pinfunction "VCC_9") (pintype "unspecified"))
      (node (ref "U3") (pin "24") (pinfunction "A9_24") (pintype "input"))
      (node (ref "U3") (pin "28") (pinfunction "BC2_28") (pintype "input"))
      (node (ref "U3") (pin "40") (pinfunction "Vcc_40") (pintype "bidirectional"))
      (node (ref "U4") (pin "33") (pinfunction "VCC_33") (pintype "unspecified"))
      (node (ref "U5") (pin "28") (pinfunction "VCC_28") (pintype "unspecified"))
      (node (ref "U6") (pin "28") (pinfunction "VCC_28") (pintype "unspecified"))
      (node (ref "U7") (pin "28") (pinfunction "VCC_28") (pintype "unspecified"))
      (node (ref "U8") (pin "28") (pinfunction "VCC_28") (pintype "unspecified"))
      (node (ref "U9") (pin "28") (pinfunction "VCC_28") (pintype "unspecified"))
      (node (ref "YM2612_IO_PORT") (pin "1") (pinfunction "1_1") (pintype "unspecified"))
    )
    (net (code "136") (name "unconnected-(ON/OFF-Pad3)") (class "Default")
      (node (ref "ON/OFF") (pin "3") (pinfunction "3_3") (pintype "unspecified+no_connect"))
    )
    (net (code "137") (name "unconnected-(ON/OFF-Pad4)") (class "Default")
      (node (ref "ON/OFF") (pin "4") (pinfunction "4_4") (pintype "unspecified+no_connect"))
    )
    (net (code "138") (name "unconnected-(ON/OFF-Pad5)") (class "Default")
      (node (ref "ON/OFF") (pin "5") (pinfunction "5_5") (pintype "unspecified+no_connect"))
    )
    (net (code "139") (name "unconnected-(OSC1-Tri-state-Pad1)") (class "Default")
      (node (ref "OSC1") (pin "1") (pinfunction "Tri-state_1") (pintype "unspecified+no_connect"))
    )
    (net (code "140") (name "unconnected-(U1-BUSACK-Pad23)") (class "Default")
      (node (ref "U1") (pin "23") (pinfunction "BUSACK_23") (pintype "output+no_connect"))
    )
    (net (code "141") (name "unconnected-(U1-HALT-Pad18)") (class "Default")
      (node (ref "U1") (pin "18") (pinfunction "HALT_18") (pintype "output+no_connect"))
    )
    (net (code "142") (name "unconnected-(U1-RFSH-Pad28)") (class "Default")
      (node (ref "U1") (pin "28") (pinfunction "RFSH_28") (pintype "output+no_connect"))
    )
    (net (code "143") (name "unconnected-(U2-ARDY-Pad18)") (class "Default")
      (node (ref "U2") (pin "18") (pinfunction "ARDY_18") (pintype "unspecified+no_connect"))
    )
    (net (code "144") (name "unconnected-(U2-BRDY-Pad21)") (class "Default")
      (node (ref "U2") (pin "21") (pinfunction "BRDY_21") (pintype "unspecified+no_connect"))
    )
    (net (code "145") (name "unconnected-(U2-IEO-Pad22)") (class "Default")
      (node (ref "U2") (pin "22") (pinfunction "IEO_22") (pintype "unspecified+no_connect"))
    )
    (net (code "146") (name "unconnected-(U4-CPUCLK-Pad38)") (class "Default")
      (node (ref "U4") (pin "38") (pinfunction "CPUCLK_38") (pintype "unspecified+no_connect"))
    )
    (net (code "147") (name "unconnected-(U4-EXTVDP-Pad35)") (class "Default")
      (node (ref "U4") (pin "35") (pinfunction "EXTVDP_35") (pintype "unspecified+no_connect"))
    )
    (net (code "148") (name "unconnected-(U4-GROMCLK-Pad37)") (class "Default")
      (node (ref "U4") (pin "37") (pinfunction "GROMCLK_37") (pintype "unspecified+no_connect"))
    )
    (net (code "149") (name "unconnected-(U5-NC-Pad1)") (class "Default")
      (node (ref "U5") (pin "1") (pinfunction "NC_1") (pintype "unspecified+no_connect"))
    )
    (net (code "150") (name "unconnected-(U5-NC-Pad26)") (class "Default")
      (node (ref "U5") (pin "26") (pinfunction "NC_26") (pintype "unspecified+no_connect"))
    )
    (net (code "151") (name "unconnected-(U6-NC-Pad1)") (class "Default")
      (node (ref "U6") (pin "1") (pinfunction "NC_1") (pintype "unspecified+no_connect"))
    )
    (net (code "152") (name "unconnected-(U6-NC-Pad26)") (class "Default")
      (node (ref "U6") (pin "26") (pinfunction "NC_26") (pintype "unspecified+no_connect"))
    )
    (net (code "153") (name "unconnected-(U7-NC-Pad1)") (class "Default")
      (node (ref "U7") (pin "1") (pinfunction "NC_1") (pintype "unspecified+no_connect"))
    )
    (net (code "154") (name "unconnected-(U7-NC-Pad26)") (class "Default")
      (node (ref "U7") (pin "26") (pinfunction "NC_26") (pintype "unspecified+no_connect"))
    )
    (net (code "155") (name "unconnected-(U8-NC-Pad1)") (class "Default")
      (node (ref "U8") (pin "1") (pinfunction "NC_1") (pintype "unspecified+no_connect"))
    )
    (net (code "156") (name "unconnected-(U8-NC-Pad26)") (class "Default")
      (node (ref "U8") (pin "26") (pinfunction "NC_26") (pintype "unspecified+no_connect"))
    )
    (net (code "157") (name "unconnected-(U14-3A-Pad9)") (class "Default")
      (node (ref "U14") (pin "9") (pinfunction "3A_9") (pintype "unspecified+no_connect"))
    )
    (net (code "158") (name "unconnected-(U14-3B-Pad10)") (class "Default")
      (node (ref "U14") (pin "10") (pinfunction "3B_10") (pintype "unspecified+no_connect"))
    )
    (net (code "159") (name "unconnected-(U14-3C-Pad11)") (class "Default")
      (node (ref "U14") (pin "11") (pinfunction "3C_11") (pintype "unspecified+no_connect"))
    )
    (net (code "160") (name "unconnected-(U14-3Y-Pad8)") (class "Default")
      (node (ref "U14") (pin "8") (pinfunction "3Y_8") (pintype "unspecified+no_connect"))
    )
    (net (code "161") (name "unconnected-(U15-5A-Pad11)") (class "Default")
      (node (ref "U15") (pin "11") (pinfunction "5A_11") (pintype "unspecified+no_connect"))
    )
    (net (code "162") (name "unconnected-(U15-5Y-Pad10)") (class "Default")
      (node (ref "U15") (pin "10") (pinfunction "5Y_10") (pintype "unspecified+no_connect"))
    )
    (net (code "163") (name "unconnected-(U15-6A-Pad13)") (class "Default")
      (node (ref "U15") (pin "13") (pinfunction "6A_13") (pintype "unspecified+no_connect"))
    )
    (net (code "164") (name "unconnected-(U15-6Y-Pad12)") (class "Default")
      (node (ref "U15") (pin "12") (pinfunction "6Y_12") (pintype "unspecified+no_connect"))
    )
    (net (code "165") (name "unconnected-(U17-Y6-Pad9)") (class "Default")
      (node (ref "U17") (pin "9") (pinfunction "Y6_9") (pintype "unspecified"))
    )
    (net (code "166") (name "unconnected-(U17-Y7-Pad7)") (class "Default")
      (node (ref "U17") (pin "7") (pinfunction "Y7_7") (pintype "unspecified"))
    )
    (net (code "167") (name "unconnected-(U18-3A-Pad9)") (class "Default")
      (node (ref "U18") (pin "9") (pinfunction "3A_9") (pintype "unspecified+no_connect"))
    )
    (net (code "168") (name "unconnected-(U18-3B-Pad10)") (class "Default")
      (node (ref "U18") (pin "10") (pinfunction "3B_10") (pintype "unspecified+no_connect"))
    )
    (net (code "169") (name "unconnected-(U18-3Y-Pad8)") (class "Default")
      (node (ref "U18") (pin "8") (pinfunction "3Y_8") (pintype "unspecified+no_connect"))
    )
    (net (code "170") (name "unconnected-(U18-4A-Pad12)") (class "Default")
      (node (ref "U18") (pin "12") (pinfunction "4A_12") (pintype "unspecified+no_connect"))
    )
    (net (code "171") (name "unconnected-(U18-4B-Pad13)") (class "Default")
      (node (ref "U18") (pin "13") (pinfunction "4B_13") (pintype "unspecified+no_connect"))
    )
    (net (code "172") (name "unconnected-(U18-4Y-Pad11)") (class "Default")
      (node (ref "U18") (pin "11") (pinfunction "4Y_11") (pintype "unspecified+no_connect"))
    )
  )
)
